# Central_Board.net
KiCad netlist of a schematic drawn in EAGLE
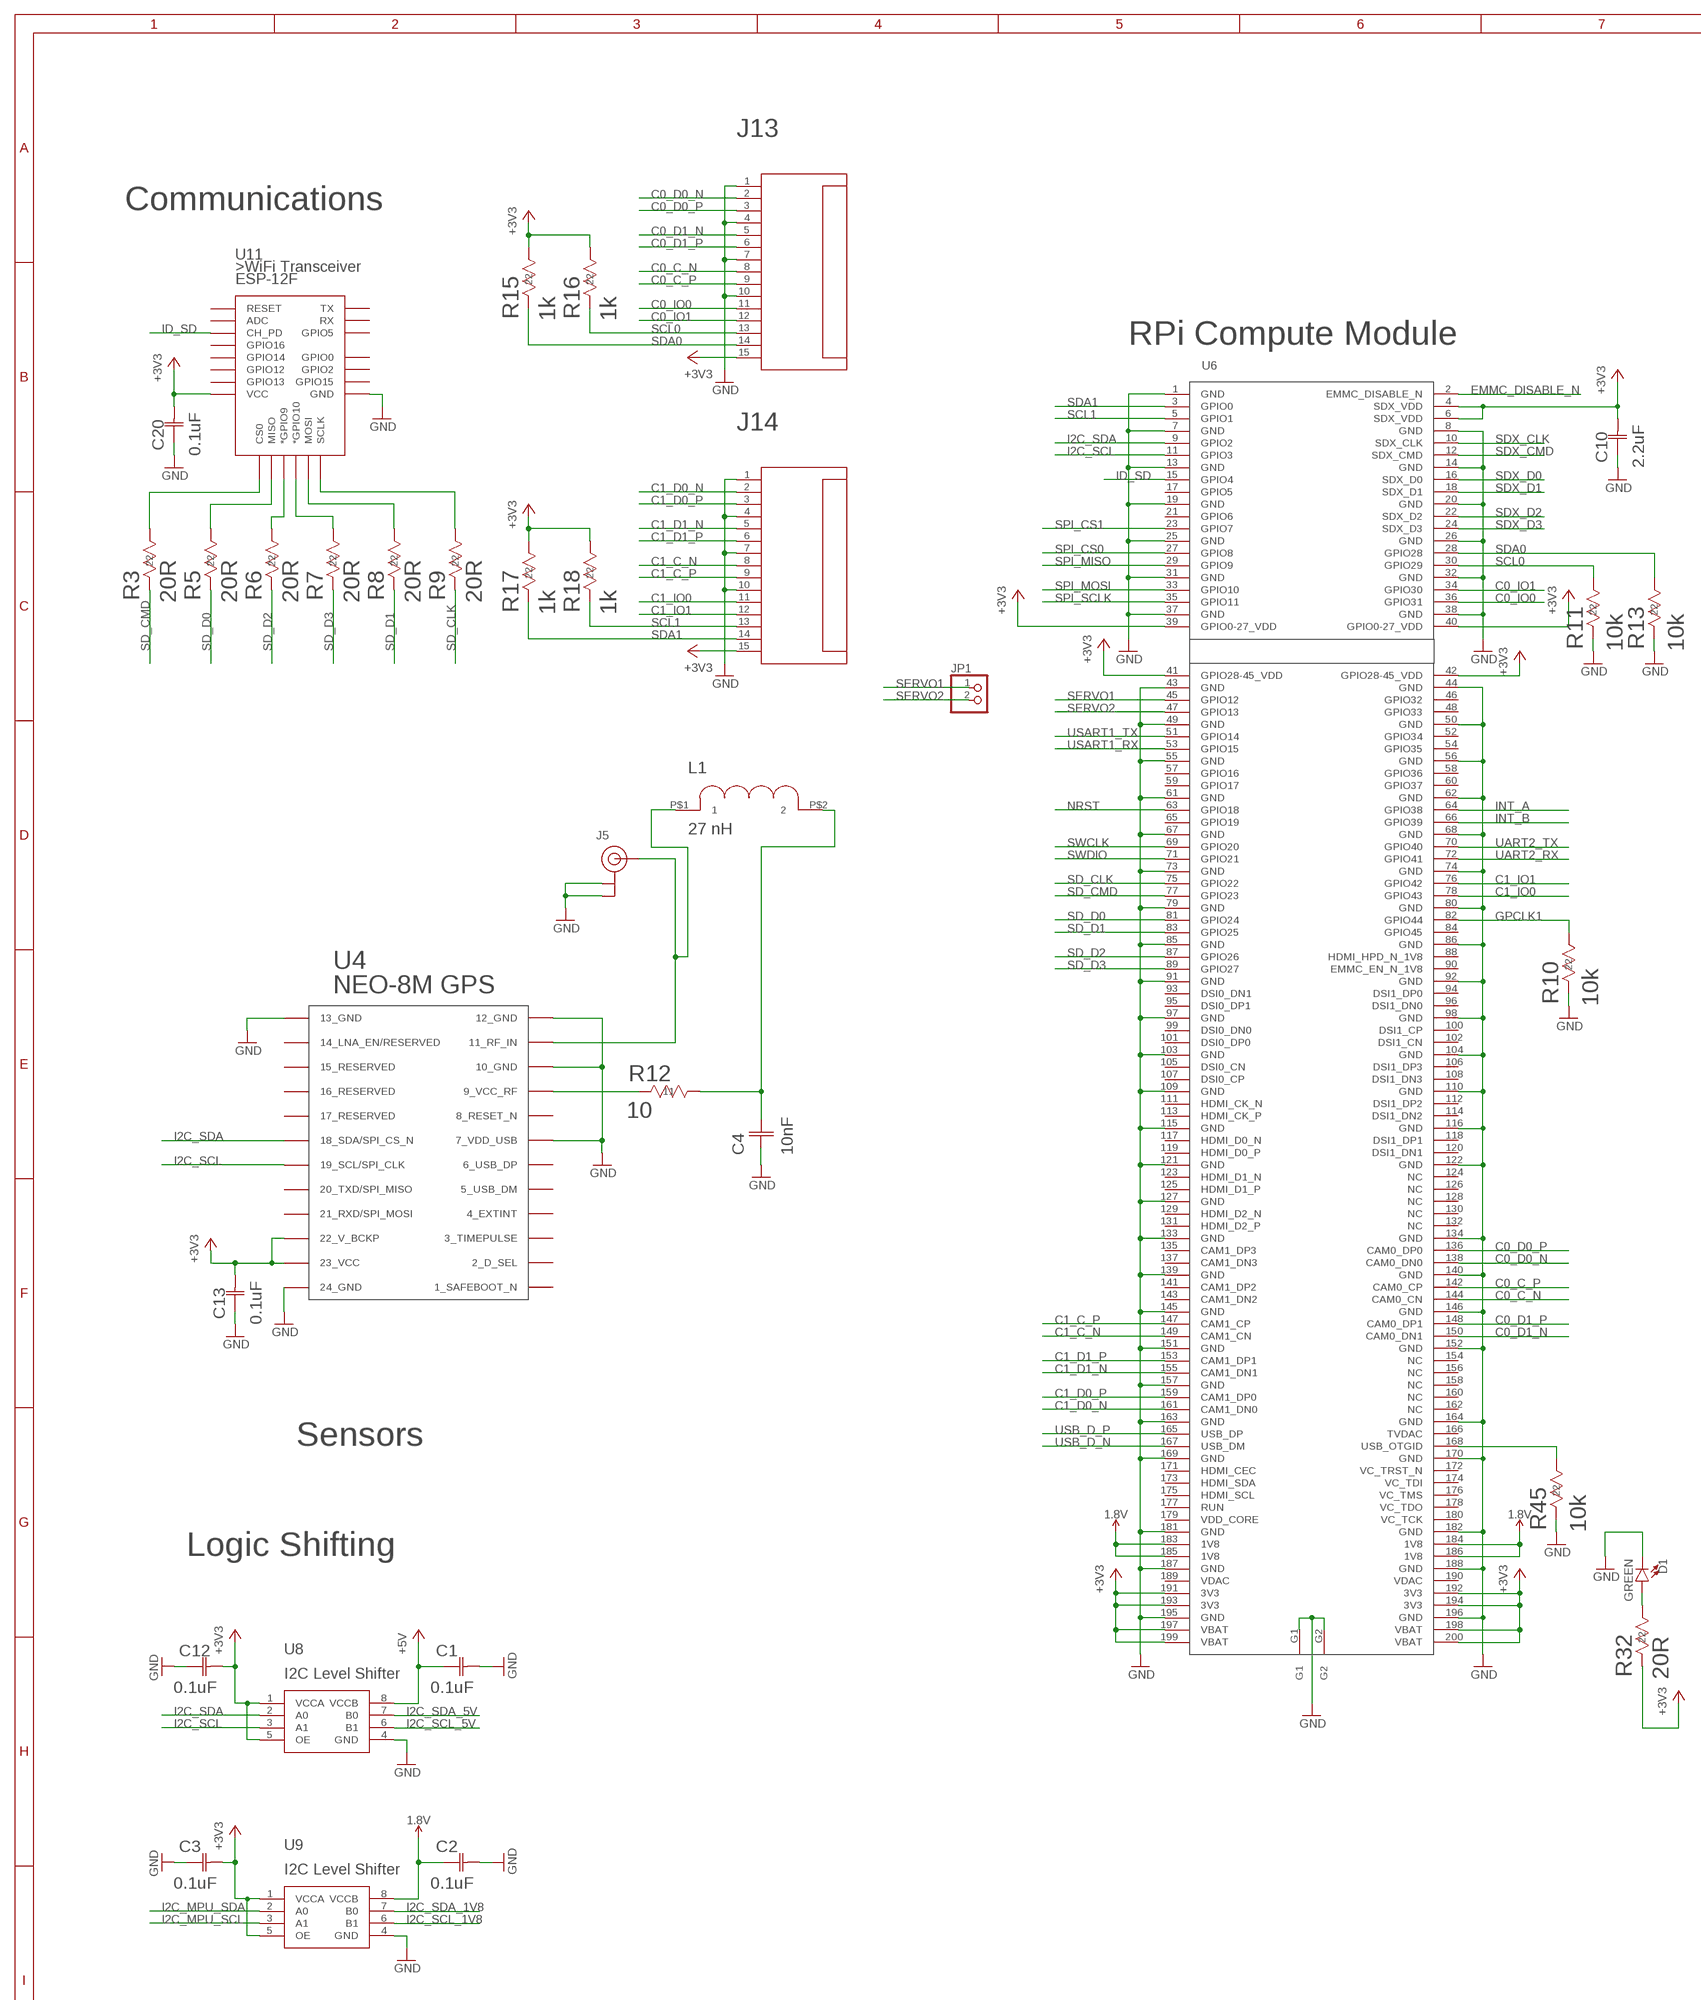
[diagram p0: schematic, sheet 1, part 1 of 2]
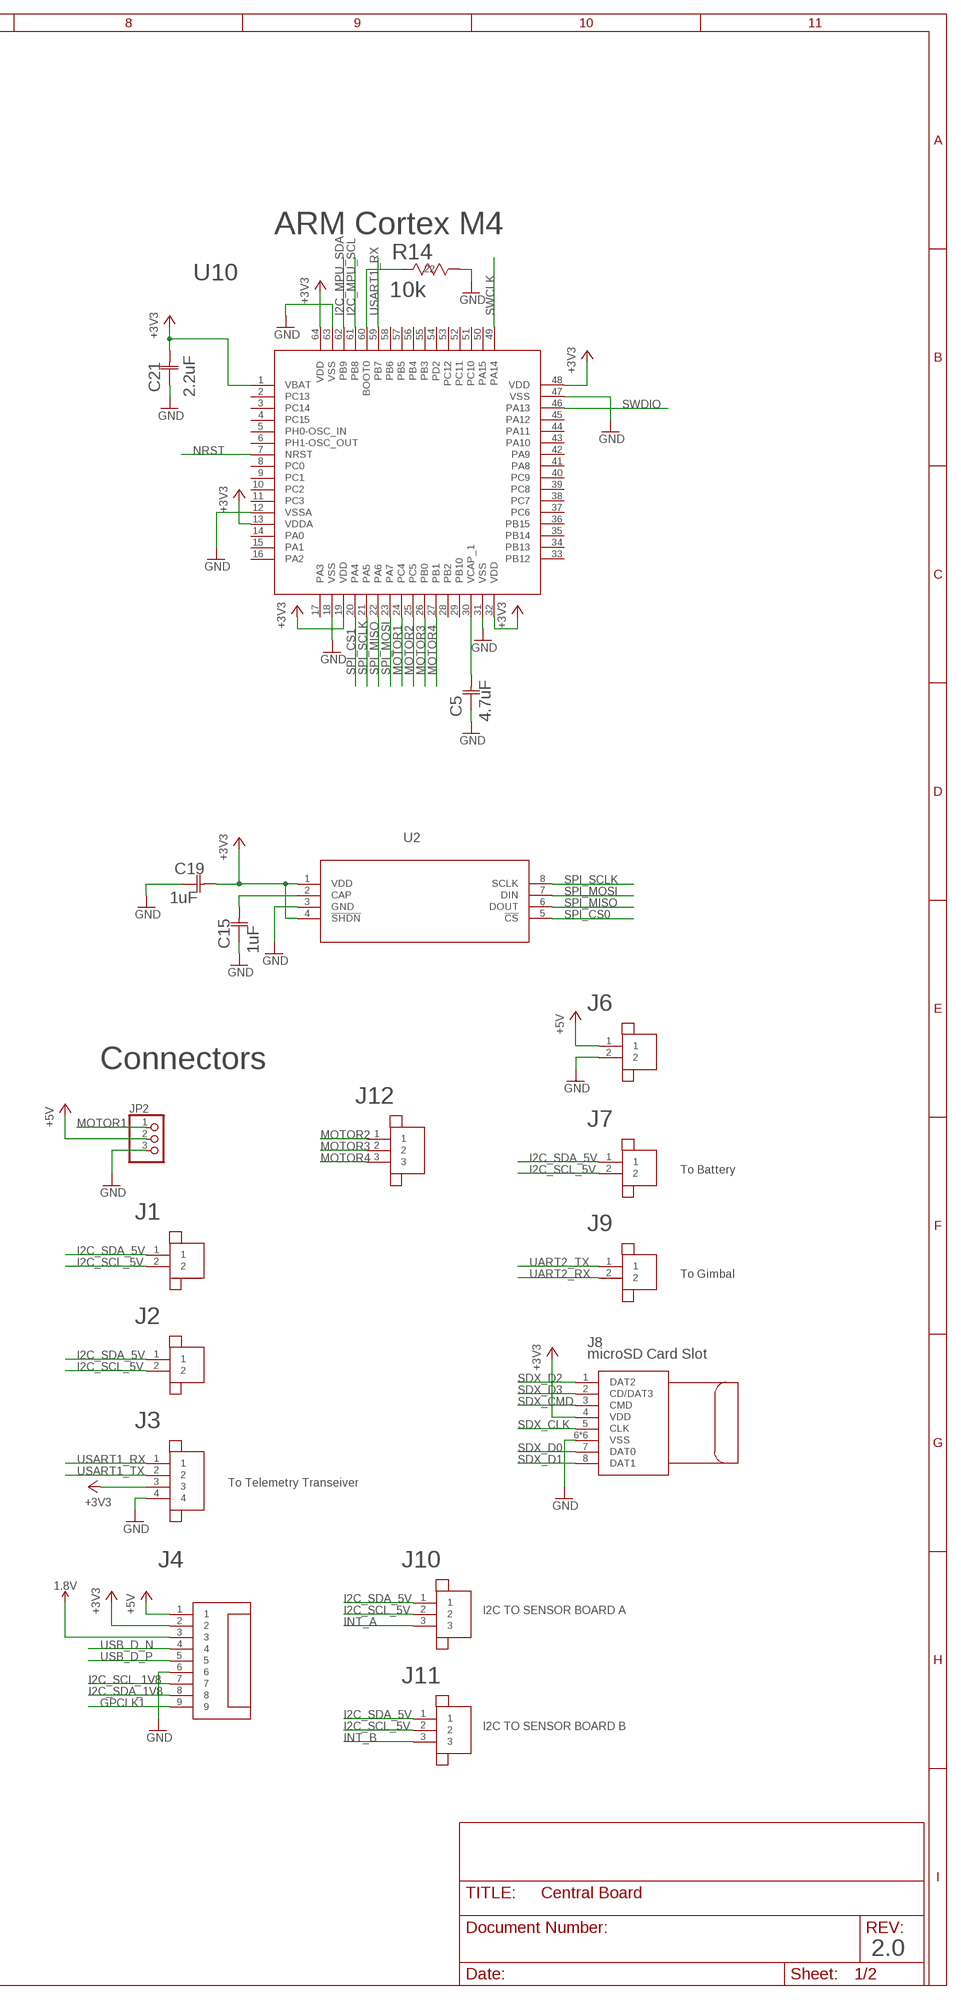
[diagram p1: schematic, sheet 1, part 2 of 2]
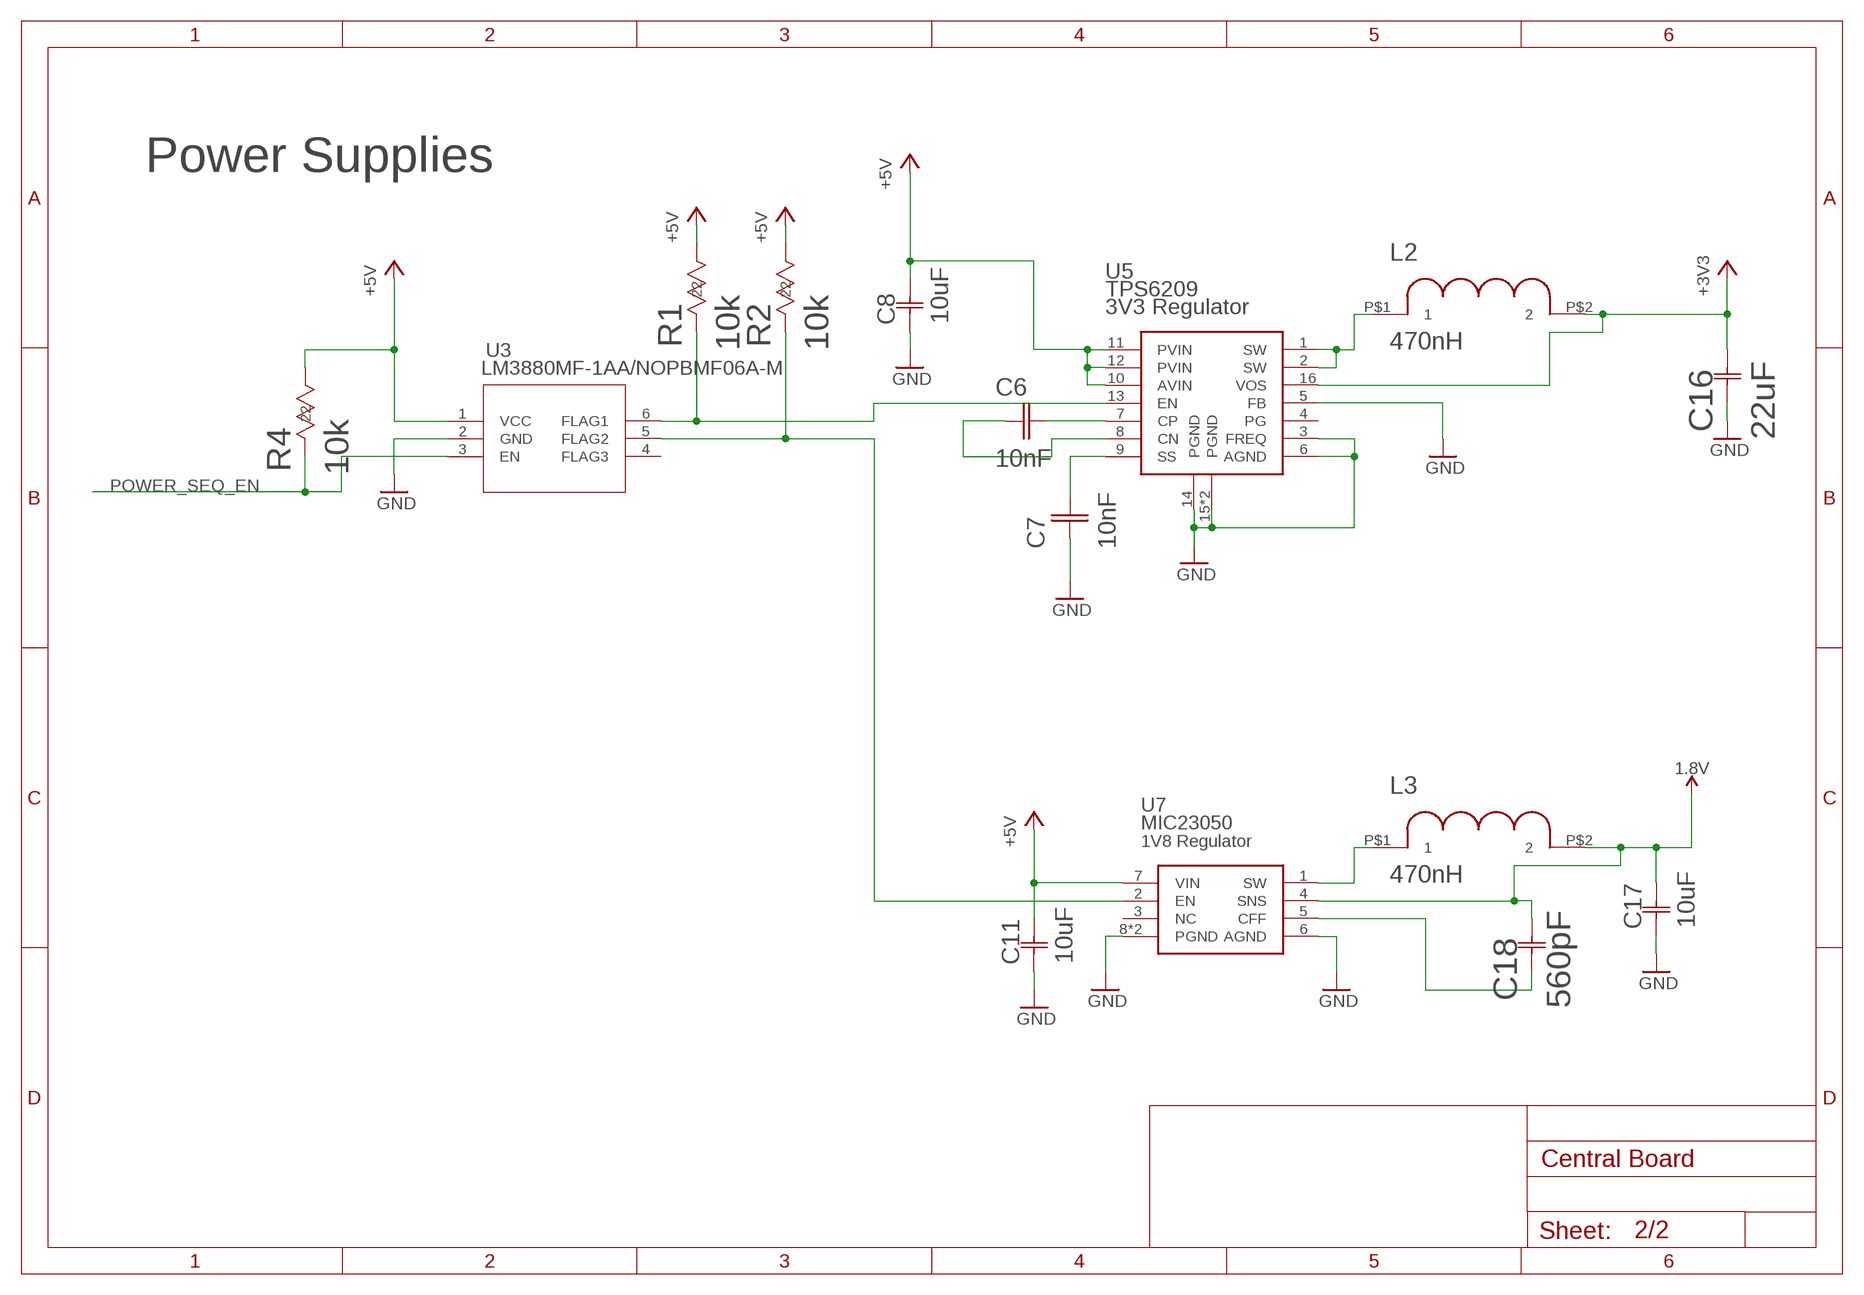
[diagram p2: schematic, sheet 2]

(export (version "E")
  (design (tool "Eeschema 10.0.6"))
  (components
    (comp (ref "C1")
      (value "0.1uF")
      (footprint "eagle-import:0805")
      (fields
        (field (name "MANUFACTURER_PART_NUMBER") "08055C104KAT2A")
        (field (name "COPYRIGHT") "Copyright C 2015 Accelerated Designs. All rights reserved")
      )
      (libsource (lib "eagle-import") (part "08055C104KAT2A"))
    )
    (comp (ref "C2")
      (value "0.1uF")
      (footprint "eagle-import:0805")
      (fields
        (field (name "MANUFACTURER_PART_NUMBER") "08055C104KAT2A")
        (field (name "COPYRIGHT") "Copyright C 2015 Accelerated Designs. All rights reserved")
      )
      (libsource (lib "eagle-import") (part "08055C104KAT2A"))
    )
    (comp (ref "C3")
      (value "0.1uF")
      (footprint "eagle-import:0805")
      (fields
        (field (name "MANUFACTURER_PART_NUMBER") "08055C104KAT2A")
        (field (name "COPYRIGHT") "Copyright C 2015 Accelerated Designs. All rights reserved")
      )
      (libsource (lib "eagle-import") (part "08055C104KAT2A"))
    )
    (comp (ref "C4")
      (value "10nF")
      (footprint "eagle-import:0603_CAPACITOR")
      (libsource (lib "eagle-import") (part "10NF_CAPACITOR"))
    )
    (comp (ref "C5")
      (value "4.7uF")
      (footprint "eagle-import:0603-M")
      (fields (field (name "MANUFACTURER_PART_NUMBER") "06036D475KAT2A"))
      (libsource (lib "eagle-import") (part "06036D475KAT2A0603-M"))
    )
    (comp (ref "C10")
      (value "2.2uF")
      (footprint "eagle-import:G-188-M")
      (fields
        (field (name "MANUFACTURER_PART_NUMBER") "GRM188R61C225KE15J")
        (field (name "COPYRIGHT") "Copyright C 2015 Accelerated Designs. All rights reserved")
      )
      (libsource (lib "eagle-import") (part "GRM188R61C225KE15JG-188-M"))
    )
    (comp (ref "C12")
      (value "0.1uF")
      (footprint "eagle-import:0805")
      (fields
        (field (name "MANUFACTURER_PART_NUMBER") "08055C104KAT2A")
        (field (name "COPYRIGHT") "Copyright C 2015 Accelerated Designs. All rights reserved")
      )
      (libsource (lib "eagle-import") (part "08055C104KAT2A"))
    )
    (comp (ref "C13")
      (value "0.1uF")
      (footprint "eagle-import:0805")
      (fields
        (field (name "MANUFACTURER_PART_NUMBER") "08055C104KAT2A")
        (field (name "COPYRIGHT") "Copyright C 2015 Accelerated Designs. All rights reserved")
      )
      (libsource (lib "eagle-import") (part "08055C104KAT2A"))
    )
    (comp (ref "C15")
      (value "1uF")
      (footprint "eagle-import:YAG_CC0805")
      (fields
        (field (name "MANUFACTURER_PART_NUMBER") "CC0805KKX7R7BB105")
        (field (name "COPYRIGHT") "Copyright C 2015 Accelerated Designs. All rights reserved")
      )
      (libsource (lib "eagle-import") (part "CC0805KKX7R7BB105"))
    )
    (comp (ref "C19")
      (value "1uF")
      (footprint "eagle-import:YAG_CC0805")
      (fields
        (field (name "MANUFACTURER_PART_NUMBER") "CC0805KKX7R7BB105")
        (field (name "COPYRIGHT") "Copyright C 2015 Accelerated Designs. All rights reserved")
      )
      (libsource (lib "eagle-import") (part "CC0805KKX7R7BB105"))
    )
    (comp (ref "C20")
      (value "0.1uF")
      (footprint "eagle-import:0805")
      (fields
        (field (name "MANUFACTURER_PART_NUMBER") "08055C104KAT2A")
        (field (name "COPYRIGHT") "Copyright C 2015 Accelerated Designs. All rights reserved")
      )
      (libsource (lib "eagle-import") (part "08055C104KAT2A"))
    )
    (comp (ref "C21")
      (value "2.2uF")
      (footprint "eagle-import:G-188-M")
      (fields
        (field (name "MANUFACTURER_PART_NUMBER") "GRM188R61C225KE15J")
        (field (name "COPYRIGHT") "Copyright C 2015 Accelerated Designs. All rights reserved")
      )
      (libsource (lib "eagle-import") (part "GRM188R61C225KE15JG-188-M"))
    )
    (comp (ref "D1")
      (value "GREEN")
      (footprint "eagle-import:LED-0603")
      (libsource (lib "eagle-import") (part "LED-GREEN0603"))
    )
    (comp (ref "J1")
      (value "JST_SH_2POS")
      (footprint "eagle-import:JST_SH_2POS")
      (libsource (lib "eagle-import") (part "JST_SH_2POS"))
    )
    (comp (ref "J2")
      (value "JST_SH_2POS")
      (footprint "eagle-import:JST_SH_2POS")
      (libsource (lib "eagle-import") (part "JST_SH_2POS"))
    )
    (comp (ref "J3")
      (value "JST_SH_4POS")
      (footprint "eagle-import:JST_SH_4POS")
      (libsource (lib "eagle-import") (part "JST_SH_4POS"))
    )
    (comp (ref "J4")
      (value "9POS_FFC_CONNECTOR")
      (footprint "eagle-import:9POS_FFC_CONNECTOR")
      (libsource (lib "eagle-import") (part "9POS_FFC_CONNECTOR"))
    )
    (comp (ref "J5")
      (value "U.FL")
      (footprint "eagle-import:U.FL")
      (libsource (lib "eagle-import") (part "U.FL"))
    )
    (comp (ref "J6")
      (value "JST_SH_2POS")
      (footprint "eagle-import:JST_SH_2POS")
      (libsource (lib "eagle-import") (part "JST_SH_2POS"))
    )
    (comp (ref "J7")
      (value "JST_SH_2POS")
      (footprint "eagle-import:JST_SH_2POS")
      (libsource (lib "eagle-import") (part "JST_SH_2POS"))
    )
    (comp (ref "J8")
      (value "MICROSD")
      (footprint "eagle-import:MICROSD")
      (libsource (lib "eagle-import") (part "MICROSD"))
    )
    (comp (ref "J9")
      (value "JST_SH_2POS")
      (footprint "eagle-import:JST_SH_2POS")
      (libsource (lib "eagle-import") (part "JST_SH_2POS"))
    )
    (comp (ref "J10")
      (value "JST_SH_3POS")
      (footprint "eagle-import:JST_SH_3POS")
      (libsource (lib "eagle-import") (part "JST_SH_3POS"))
    )
    (comp (ref "J11")
      (value "JST_SH_3POS")
      (footprint "eagle-import:JST_SH_3POS")
      (libsource (lib "eagle-import") (part "JST_SH_3POS"))
    )
    (comp (ref "J12")
      (value "JST_SH_3POS")
      (footprint "eagle-import:JST_SH_3POS")
      (libsource (lib "eagle-import") (part "JST_SH_3POS"))
    )
    (comp (ref "J13")
      (value "0526101572_15ZIF_CONNECTOR")
      (footprint "eagle-import:15POS_FFC_CONNECTOR")
      (libsource (lib "eagle-import") (part "0526101572_15ZIF_CONNECTOR"))
    )
    (comp (ref "J14")
      (value "0526101572_15ZIF_CONNECTOR")
      (footprint "eagle-import:15POS_FFC_CONNECTOR")
      (libsource (lib "eagle-import") (part "0526101572_15ZIF_CONNECTOR"))
    )
    (comp (ref "JP1")
      (value "PINHD-1X2")
      (footprint "eagle-import:1X02")
      (libsource (lib "eagle-import") (part "PINHD-1X2"))
    )
    (comp (ref "JP2")
      (value "PINHD-1X3")
      (footprint "eagle-import:1X03")
      (libsource (lib "eagle-import") (part "PINHD-1X3"))
    )
    (comp (ref "L1")
      (value "27 nH")
      (footprint "eagle-import:0402_INDUCTOR")
      (libsource (lib "eagle-import") (part "27NH_INDUCTOR"))
    )
    (comp (ref "R3")
      (value "20R")
      (footprint "eagle-import:RC0603N-M")
      (fields (field (name "MANUFACTURER_PART_NUMBER") "RC0603JR0720RL"))
      (libsource (lib "eagle-import") (part "RC0603JR-0720RLRC0603N-M"))
    )
    (comp (ref "R5")
      (value "20R")
      (footprint "eagle-import:RC0603N-M")
      (fields (field (name "MANUFACTURER_PART_NUMBER") "RC0603JR0720RL"))
      (libsource (lib "eagle-import") (part "RC0603JR-0720RLRC0603N-M"))
    )
    (comp (ref "R6")
      (value "20R")
      (footprint "eagle-import:RC0603N-M")
      (fields (field (name "MANUFACTURER_PART_NUMBER") "RC0603JR0720RL"))
      (libsource (lib "eagle-import") (part "RC0603JR-0720RLRC0603N-M"))
    )
    (comp (ref "R7")
      (value "20R")
      (footprint "eagle-import:RC0603N-M")
      (fields (field (name "MANUFACTURER_PART_NUMBER") "RC0603JR0720RL"))
      (libsource (lib "eagle-import") (part "RC0603JR-0720RLRC0603N-M"))
    )
    (comp (ref "R8")
      (value "20R")
      (footprint "eagle-import:RC0603N-M")
      (fields (field (name "MANUFACTURER_PART_NUMBER") "RC0603JR0720RL"))
      (libsource (lib "eagle-import") (part "RC0603JR-0720RLRC0603N-M"))
    )
    (comp (ref "R9")
      (value "20R")
      (footprint "eagle-import:RC0603N-M")
      (fields (field (name "MANUFACTURER_PART_NUMBER") "RC0603JR0720RL"))
      (libsource (lib "eagle-import") (part "RC0603JR-0720RLRC0603N-M"))
    )
    (comp (ref "R10")
      (value "10k")
      (footprint "eagle-import:RC0805N")
      (fields
        (field (name "DIGIKEYPARTNUMBER") "P10KDATRND")
        (field (name "MANUFACTURER_PART_NUMBER") "ERA6AEB103V")
        (field (name "TOLERANCE") "0.1%")
        (field (name "COPYRIGHT") "Copyright C 2015 Accelerated Designs. All rights reserved")
      )
      (libsource (lib "eagle-import") (part "ERA-6AEB103V"))
    )
    (comp (ref "R11")
      (value "10k")
      (footprint "eagle-import:RC0805N")
      (fields
        (field (name "DIGIKEYPARTNUMBER") "P10KDATRND")
        (field (name "MANUFACTURER_PART_NUMBER") "ERA6AEB103V")
        (field (name "TOLERANCE") "0.1%")
        (field (name "COPYRIGHT") "Copyright C 2015 Accelerated Designs. All rights reserved")
      )
      (libsource (lib "eagle-import") (part "ERA-6AEB103V"))
    )
    (comp (ref "R12")
      (value "10")
      (footprint "eagle-import:STA_RNCP0805-M")
      (fields
        (field (name "MANUFACTURER_PART_NUMBER") "RNCP0805FTD10R0")
        (field (name "COPYRIGHT") "Copyright C 2015 Accelerated Designs. All rights reserved")
      )
      (libsource (lib "eagle-import") (part "RNCP0805FTD10R0STA_RNCP0805-M"))
    )
    (comp (ref "R13")
      (value "10k")
      (footprint "eagle-import:RC0805N")
      (fields
        (field (name "DIGIKEYPARTNUMBER") "P10KDATRND")
        (field (name "MANUFACTURER_PART_NUMBER") "ERA6AEB103V")
        (field (name "TOLERANCE") "0.1%")
        (field (name "COPYRIGHT") "Copyright C 2015 Accelerated Designs. All rights reserved")
      )
      (libsource (lib "eagle-import") (part "ERA-6AEB103V"))
    )
    (comp (ref "R14")
      (value "10k")
      (footprint "eagle-import:RC0805N")
      (fields
        (field (name "DIGIKEYPARTNUMBER") "P10KDATRND")
        (field (name "MANUFACTURER_PART_NUMBER") "ERA6AEB103V")
        (field (name "TOLERANCE") "0.1%")
        (field (name "COPYRIGHT") "Copyright C 2015 Accelerated Designs. All rights reserved")
      )
      (libsource (lib "eagle-import") (part "ERA-6AEB103V"))
    )
    (comp (ref "R15")
      (value "1k")
      (footprint "eagle-import:RC0603N-M")
      (fields
        (field (name "DIGIKEYPARTNUMBER") "3111.0KGRTRND")
        (field (name "MANUFACTURER_PART_NUMBER") "RC0603JR071KL")
        (field (name "NEWARKPARTNUMBER") "14M7231")
        (field (name "COPYRIGHT") "Copyright C 2015 Accelerated Designs. All rights reserved")
      )
      (libsource (lib "eagle-import") (part "RC0603JR-071KLRC0603N-M"))
    )
    (comp (ref "R16")
      (value "1k")
      (footprint "eagle-import:RC0603N-M")
      (fields
        (field (name "DIGIKEYPARTNUMBER") "3111.0KGRTRND")
        (field (name "MANUFACTURER_PART_NUMBER") "RC0603JR071KL")
        (field (name "NEWARKPARTNUMBER") "14M7231")
        (field (name "COPYRIGHT") "Copyright C 2015 Accelerated Designs. All rights reserved")
      )
      (libsource (lib "eagle-import") (part "RC0603JR-071KLRC0603N-M"))
    )
    (comp (ref "R17")
      (value "1k")
      (footprint "eagle-import:RC0603N-M")
      (fields
        (field (name "DIGIKEYPARTNUMBER") "3111.0KGRTRND")
        (field (name "MANUFACTURER_PART_NUMBER") "RC0603JR071KL")
        (field (name "NEWARKPARTNUMBER") "14M7231")
        (field (name "COPYRIGHT") "Copyright C 2015 Accelerated Designs. All rights reserved")
      )
      (libsource (lib "eagle-import") (part "RC0603JR-071KLRC0603N-M"))
    )
    (comp (ref "R18")
      (value "1k")
      (footprint "eagle-import:RC0603N-M")
      (fields
        (field (name "DIGIKEYPARTNUMBER") "3111.0KGRTRND")
        (field (name "MANUFACTURER_PART_NUMBER") "RC0603JR071KL")
        (field (name "NEWARKPARTNUMBER") "14M7231")
        (field (name "COPYRIGHT") "Copyright C 2015 Accelerated Designs. All rights reserved")
      )
      (libsource (lib "eagle-import") (part "RC0603JR-071KLRC0603N-M"))
    )
    (comp (ref "R32")
      (value "20R")
      (footprint "eagle-import:RC0603N-M")
      (fields (field (name "MANUFACTURER_PART_NUMBER") "RC0603JR0720RL"))
      (libsource (lib "eagle-import") (part "RC0603JR-0720RLRC0603N-M"))
    )
    (comp (ref "R45")
      (value "10k")
      (footprint "eagle-import:RC0805N")
      (fields
        (field (name "DIGIKEYPARTNUMBER") "P10KDATRND")
        (field (name "MANUFACTURER_PART_NUMBER") "ERA6AEB103V")
        (field (name "TOLERANCE") "0.1%")
        (field (name "COPYRIGHT") "Copyright C 2015 Accelerated Designs. All rights reserved")
      )
      (libsource (lib "eagle-import") (part "ERA-6AEB103V"))
    )
    (comp (ref "U2")
      (value "MPL115A1LGA8-M")
      (footprint "eagle-import:LGA8-M")
      (fields (field (name "MANUFACTURER_PART_NUMBER") "mpl115a1"))
      (libsource (lib "eagle-import") (part "MPL115A1LGA8-M"))
    )
    (comp (ref "U4")
      (value "NEO-M8")
      (footprint "eagle-import:NEO-M8")
      (libsource (lib "eagle-import") (part "NEO-M8"))
    )
    (comp (ref "U6")
      (value "COMPUTE_MODULE")
      (footprint "eagle-import:SO-DIMM")
      (libsource (lib "eagle-import") (part "COMPUTE_MODULE"))
    )
    (comp (ref "U8")
      (value "FXMAR2102")
      (footprint "eagle-import:8-UMLP")
      (libsource (lib "eagle-import") (part "FXMAR2102"))
    )
    (comp (ref "U9")
      (value "FXMAR2102")
      (footprint "eagle-import:8-UMLP")
      (libsource (lib "eagle-import") (part "FXMAR2102"))
    )
    (comp (ref "U10")
      (value "STM32F446")
      (footprint "eagle-import:LQFP64")
      (libsource (lib "eagle-import") (part "STM32F446"))
    )
    (comp (ref "U11")
      (value "ESP12ESMD")
      (footprint "eagle-import:ESP12E-SMD")
      (libsource (lib "eagle-import") (part "ESP12ESMD"))
    )
    (comp (ref "C6")
      (value "10nF")
      (footprint "eagle-import:0603_CAPACITOR")
      (libsource (lib "eagle-import") (part "10NF_CAPACITOR"))
    )
    (comp (ref "C7")
      (value "10nF")
      (footprint "eagle-import:0603_CAPACITOR")
      (libsource (lib "eagle-import") (part "10NF_CAPACITOR"))
    )
    (comp (ref "C8")
      (value "10uF")
      (footprint "eagle-import:G-21")
      (fields
        (field (name "MANUFACTURER_PART_NUMBER") "GRM21BR60J106ME19L")
        (field (name "COPYRIGHT") "Copyright C 2015 Accelerated Designs. All rights reserved")
      )
      (libsource (lib "eagle-import") (part "GRM21BR60J106ME19L"))
    )
    (comp (ref "C11")
      (value "10uF")
      (footprint "eagle-import:G-21")
      (fields
        (field (name "MANUFACTURER_PART_NUMBER") "GRM21BR60J106ME19L")
        (field (name "COPYRIGHT") "Copyright C 2015 Accelerated Designs. All rights reserved")
      )
      (libsource (lib "eagle-import") (part "GRM21BR60J106ME19L"))
    )
    (comp (ref "C16")
      (value "22uF")
      (footprint "eagle-import:G-21")
      (fields
        (field (name "MANUFACTURER_PART_NUMBER") "GRM21BR60J226ME39L")
        (field (name "COPYRIGHT") "Copyright C 2015 Accelerated Designs. All rights reserved")
      )
      (libsource (lib "eagle-import") (part "GRM21BR60J226ME39L"))
    )
    (comp (ref "C17")
      (value "10uF")
      (footprint "eagle-import:G-21")
      (fields
        (field (name "MANUFACTURER_PART_NUMBER") "GRM21BR60J106ME19L")
        (field (name "COPYRIGHT") "Copyright C 2015 Accelerated Designs. All rights reserved")
      )
      (libsource (lib "eagle-import") (part "GRM21BR60J106ME19L"))
    )
    (comp (ref "C18")
      (value "560pF")
      (footprint "eagle-import:CC0402N-M")
      (fields (field (name "MANUFACTURER_PART_NUMBER") "CC0402KRX7R9BB561"))
      (libsource (lib "eagle-import") (part "CC0402KRX7R9BB561CC0402N-M"))
    )
    (comp (ref "L2")
      (value "470nH")
      (footprint "eagle-import:1008_INDUCTOR")
      (libsource (lib "eagle-import") (part "470NH_INDUCTOR"))
    )
    (comp (ref "L3")
      (value "470nH")
      (footprint "eagle-import:1008_INDUCTOR")
      (libsource (lib "eagle-import") (part "470NH_INDUCTOR"))
    )
    (comp (ref "R1")
      (value "10k")
      (footprint "eagle-import:RC0805N")
      (fields
        (field (name "DIGIKEYPARTNUMBER") "P10KDATRND")
        (field (name "MANUFACTURER_PART_NUMBER") "ERA6AEB103V")
        (field (name "TOLERANCE") "0.1%")
        (field (name "COPYRIGHT") "Copyright C 2015 Accelerated Designs. All rights reserved")
      )
      (libsource (lib "eagle-import") (part "ERA-6AEB103V"))
    )
    (comp (ref "R2")
      (value "10k")
      (footprint "eagle-import:RC0805N")
      (fields
        (field (name "DIGIKEYPARTNUMBER") "P10KDATRND")
        (field (name "MANUFACTURER_PART_NUMBER") "ERA6AEB103V")
        (field (name "TOLERANCE") "0.1%")
        (field (name "COPYRIGHT") "Copyright C 2015 Accelerated Designs. All rights reserved")
      )
      (libsource (lib "eagle-import") (part "ERA-6AEB103V"))
    )
    (comp (ref "R4")
      (value "10k")
      (footprint "eagle-import:RC0805N")
      (fields
        (field (name "DIGIKEYPARTNUMBER") "P10KDATRND")
        (field (name "MANUFACTURER_PART_NUMBER") "ERA6AEB103V")
        (field (name "TOLERANCE") "0.1%")
        (field (name "COPYRIGHT") "Copyright C 2015 Accelerated Designs. All rights reserved")
      )
      (libsource (lib "eagle-import") (part "ERA-6AEB103V"))
    )
    (comp (ref "U3")
      (value "LM3880MF-1AA/NOPBMF06A-M")
      (footprint "eagle-import:MF06A-M")
      (fields (field (name "MANUFACTURER_PART_NUMBER") "lm3880mf1aaNOPB"))
      (libsource (lib "eagle-import") (part "LM3880MF-1AA/NOPBMF06A-M"))
    )
    (comp (ref "U5")
      (value "TPS6209")
      (footprint "eagle-import:VQFN16")
      (libsource (lib "eagle-import") (part "TPS6209"))
    )
    (comp (ref "U7")
      (value "MIC23050")
      (footprint "eagle-import:MLF(ML)_8PIN")
      (libsource (lib "eagle-import") (part "MIC23050"))
    )
  )
  (nets
    (net (code "1") (name "+3V3") (class "Default")
      (node (ref "C10") (pin "2") (pinfunction "22_2") (pintype "passive"))
      (node (ref "C12") (pin "2") (pinfunction "2_2") (pintype "passive"))
      (node (ref "C13") (pin "2") (pinfunction "2_2") (pintype "passive"))
      (node (ref "C16") (pin "2") (pinfunction "22_2") (pintype "passive"))
      (node (ref "C19") (pin "2") (pinfunction "22_2") (pintype "passive"))
      (node (ref "C20") (pin "2") (pinfunction "2_2") (pintype "passive"))
      (node (ref "C21") (pin "2") (pinfunction "22_2") (pintype "passive"))
      (node (ref "C3") (pin "2") (pinfunction "2_2") (pintype "passive"))
      (node (ref "J13") (pin "15") (pinfunction "15_15") (pintype "bidirectional"))
      (node (ref "J14") (pin "15") (pinfunction "15_15") (pintype "bidirectional"))
      (node (ref "J3") (pin "3") (pinfunction "3_3") (pintype "bidirectional"))
      (node (ref "J4") (pin "2") (pinfunction "2_2") (pintype "bidirectional"))
      (node (ref "J8") (pin "4") (pinfunction "VDD_4") (pintype "bidirectional"))
      (node (ref "L2") (pin "P$2") (pinfunction "2_P$2") (pintype "passive"))
      (node (ref "R15") (pin "1") (pinfunction "11_1") (pintype "passive"))
      (node (ref "R16") (pin "1") (pinfunction "11_1") (pintype "passive"))
      (node (ref "R17") (pin "1") (pinfunction "11_1") (pintype "passive"))
      (node (ref "R18") (pin "1") (pinfunction "11_1") (pintype "passive"))
      (node (ref "R32") (pin "2") (pinfunction "22_2") (pintype "passive"))
      (node (ref "U10") (pin "1") (pinfunction "VBAT_1") (pintype "bidirectional"))
      (node (ref "U10") (pin "13") (pinfunction "VDDA_13") (pintype "bidirectional"))
      (node (ref "U10") (pin "19") (pinfunction "VDD_19") (pintype "bidirectional"))
      (node (ref "U10") (pin "32") (pinfunction "VDD_32") (pintype "bidirectional"))
      (node (ref "U10") (pin "48") (pinfunction "VDD_48") (pintype "bidirectional"))
      (node (ref "U10") (pin "64") (pinfunction "VDD_64") (pintype "bidirectional"))
      (node (ref "U11") (pin "VCC") (pinfunction "VCC_VCC") (pintype "bidirectional"))
      (node (ref "U2") (pin "1") (pinfunction "VDD_1") (pintype "power_in"))
      (node (ref "U2") (pin "4") (pinfunction "~{SHDN}_4") (pintype "passive"))
      (node (ref "U4") (pin "22") (pinfunction "22_V_BCKP_22") (pintype "bidirectional"))
      (node (ref "U4") (pin "23") (pinfunction "23_VCC_23") (pintype "bidirectional"))
      (node (ref "U5") (pin "16") (pinfunction "VOS_16") (pintype "bidirectional"))
      (node (ref "U6") (pin "191") (pinfunction "3V3_191") (pintype "bidirectional"))
      (node (ref "U6") (pin "192") (pinfunction "3V3_192") (pintype "bidirectional"))
      (node (ref "U6") (pin "193") (pinfunction "3V3_193") (pintype "bidirectional"))
      (node (ref "U6") (pin "194") (pinfunction "3V3_194") (pintype "bidirectional"))
      (node (ref "U6") (pin "197") (pinfunction "VBAT_197") (pintype "bidirectional"))
      (node (ref "U6") (pin "198") (pinfunction "VBAT_198") (pintype "bidirectional"))
      (node (ref "U6") (pin "199") (pinfunction "VBAT_199") (pintype "bidirectional"))
      (node (ref "U6") (pin "200") (pinfunction "VBAT_200") (pintype "bidirectional"))
      (node (ref "U6") (pin "39") (pinfunction "GPIO0-27_VDD_39") (pintype "bidirectional"))
      (node (ref "U6") (pin "4") (pinfunction "SDX_VDD_4") (pintype "bidirectional"))
      (node (ref "U6") (pin "40") (pinfunction "GPIO0-27_VDD_40") (pintype "bidirectional"))
      (node (ref "U6") (pin "41") (pinfunction "GPIO28-45_VDD_41") (pintype "bidirectional"))
      (node (ref "U6") (pin "42") (pinfunction "GPIO28-45_VDD_42") (pintype "bidirectional"))
      (node (ref "U6") (pin "6") (pinfunction "SDX_VDD_6") (pintype "bidirectional"))
      (node (ref "U8") (pin "1") (pinfunction "VCCA_1") (pintype "bidirectional"))
      (node (ref "U8") (pin "5") (pinfunction "OE_5") (pintype "bidirectional"))
      (node (ref "U9") (pin "1") (pinfunction "VCCA_1") (pintype "bidirectional"))
      (node (ref "U9") (pin "5") (pinfunction "OE_5") (pintype "bidirectional"))
    )
    (net (code "2") (name "+5V") (class "Default")
      (node (ref "C1") (pin "1") (pinfunction "1_1") (pintype "passive"))
      (node (ref "C11") (pin "2") (pinfunction "22_2") (pintype "passive"))
      (node (ref "C8") (pin "2") (pinfunction "22_2") (pintype "passive"))
      (node (ref "J4") (pin "1") (pinfunction "1_1") (pintype "bidirectional"))
      (node (ref "J6") (pin "1") (pinfunction "1_1") (pintype "bidirectional"))
      (node (ref "JP2") (pin "2") (pinfunction "2_2") (pintype "passive"))
      (node (ref "R1") (pin "1") (pinfunction "11_1") (pintype "passive"))
      (node (ref "R2") (pin "1") (pinfunction "11_1") (pintype "passive"))
      (node (ref "R4") (pin "1") (pinfunction "11_1") (pintype "passive"))
      (node (ref "U3") (pin "1") (pinfunction "VCC_1") (pintype "power_in"))
      (node (ref "U5") (pin "10") (pinfunction "AVIN_10") (pintype "bidirectional"))
      (node (ref "U5") (pin "11") (pinfunction "PVIN_11") (pintype "bidirectional"))
      (node (ref "U5") (pin "12") (pinfunction "PVIN_12") (pintype "bidirectional"))
      (node (ref "U7") (pin "7") (pinfunction "VIN_7") (pintype "bidirectional"))
      (node (ref "U8") (pin "8") (pinfunction "VCCB_8") (pintype "bidirectional"))
    )
    (net (code "3") (name "1.8V") (class "Default")
      (node (ref "C17") (pin "2") (pinfunction "22_2") (pintype "passive"))
      (node (ref "C18") (pin "2") (pinfunction "22_2") (pintype "passive"))
      (node (ref "C2") (pin "1") (pinfunction "1_1") (pintype "passive"))
      (node (ref "J4") (pin "3") (pinfunction "3_3") (pintype "bidirectional"))
      (node (ref "L3") (pin "P$2") (pinfunction "2_P$2") (pintype "passive"))
      (node (ref "U6") (pin "183") (pinfunction "1V8_183") (pintype "bidirectional"))
      (node (ref "U6") (pin "184") (pinfunction "1V8_184") (pintype "bidirectional"))
      (node (ref "U6") (pin "185") (pinfunction "1V8_185") (pintype "bidirectional"))
      (node (ref "U6") (pin "186") (pinfunction "1V8_186") (pintype "bidirectional"))
      (node (ref "U7") (pin "4") (pinfunction "SNS_4") (pintype "bidirectional"))
      (node (ref "U9") (pin "8") (pinfunction "VCCB_8") (pintype "bidirectional"))
    )
    (net (code "4") (name "C0_C_N") (class "Default")
      (node (ref "J13") (pin "8") (pinfunction "8_8") (pintype "bidirectional"))
      (node (ref "U6") (pin "144") (pinfunction "CAM0_CN_144") (pintype "bidirectional"))
    )
    (net (code "5") (name "C0_C_P") (class "Default")
      (node (ref "J13") (pin "9") (pinfunction "9_9") (pintype "bidirectional"))
      (node (ref "U6") (pin "142") (pinfunction "CAM0_CP_142") (pintype "bidirectional"))
    )
    (net (code "6") (name "C0_D0_N") (class "Default")
      (node (ref "J13") (pin "2") (pinfunction "2_2") (pintype "bidirectional"))
      (node (ref "U6") (pin "138") (pinfunction "CAM0_DN0_138") (pintype "bidirectional"))
    )
    (net (code "7") (name "C0_D0_P") (class "Default")
      (node (ref "J13") (pin "3") (pinfunction "3_3") (pintype "bidirectional"))
      (node (ref "U6") (pin "136") (pinfunction "CAM0_DP0_136") (pintype "bidirectional"))
    )
    (net (code "8") (name "C0_D1_N") (class "Default")
      (node (ref "J13") (pin "5") (pinfunction "5_5") (pintype "bidirectional"))
      (node (ref "U6") (pin "150") (pinfunction "CAM0_DN1_150") (pintype "bidirectional"))
    )
    (net (code "9") (name "C0_D1_P") (class "Default")
      (node (ref "J13") (pin "6") (pinfunction "6_6") (pintype "bidirectional"))
      (node (ref "U6") (pin "148") (pinfunction "CAM0_DP1_148") (pintype "bidirectional"))
    )
    (net (code "10") (name "C0_IO0") (class "Default")
      (node (ref "J13") (pin "11") (pinfunction "11_11") (pintype "bidirectional"))
      (node (ref "U6") (pin "36") (pinfunction "GPIO31_36") (pintype "bidirectional"))
    )
    (net (code "11") (name "C0_IO1") (class "Default")
      (node (ref "J13") (pin "12") (pinfunction "12_12") (pintype "bidirectional"))
      (node (ref "U6") (pin "34") (pinfunction "GPIO30_34") (pintype "bidirectional"))
    )
    (net (code "12") (name "C1_C_N") (class "Default")
      (node (ref "J14") (pin "8") (pinfunction "8_8") (pintype "bidirectional"))
      (node (ref "U6") (pin "149") (pinfunction "CAM1_CN_149") (pintype "bidirectional"))
    )
    (net (code "13") (name "C1_C_P") (class "Default")
      (node (ref "J14") (pin "9") (pinfunction "9_9") (pintype "bidirectional"))
      (node (ref "U6") (pin "147") (pinfunction "CAM1_CP_147") (pintype "bidirectional"))
    )
    (net (code "14") (name "C1_D0_N") (class "Default")
      (node (ref "J14") (pin "2") (pinfunction "2_2") (pintype "bidirectional"))
      (node (ref "U6") (pin "161") (pinfunction "CAM1_DN0_161") (pintype "bidirectional"))
    )
    (net (code "15") (name "C1_D0_P") (class "Default")
      (node (ref "J14") (pin "3") (pinfunction "3_3") (pintype "bidirectional"))
      (node (ref "U6") (pin "159") (pinfunction "CAM1_DP0_159") (pintype "bidirectional"))
    )
    (net (code "16") (name "C1_D1_N") (class "Default")
      (node (ref "J14") (pin "5") (pinfunction "5_5") (pintype "bidirectional"))
      (node (ref "U6") (pin "155") (pinfunction "CAM1_DN1_155") (pintype "bidirectional"))
    )
    (net (code "17") (name "C1_D1_P") (class "Default")
      (node (ref "J14") (pin "6") (pinfunction "6_6") (pintype "bidirectional"))
      (node (ref "U6") (pin "153") (pinfunction "CAM1_DP1_153") (pintype "bidirectional"))
    )
    (net (code "18") (name "C1_IO0") (class "Default")
      (node (ref "J14") (pin "11") (pinfunction "11_11") (pintype "bidirectional"))
      (node (ref "U6") (pin "78") (pinfunction "GPIO43_78") (pintype "bidirectional"))
    )
    (net (code "19") (name "C1_IO1") (class "Default")
      (node (ref "J14") (pin "12") (pinfunction "12_12") (pintype "bidirectional"))
      (node (ref "U6") (pin "76") (pinfunction "GPIO42_76") (pintype "bidirectional"))
    )
    (net (code "20") (name "EMMC_DISABLE_N") (class "Default")
      (node (ref "U6") (pin "2") (pinfunction "EMMC_DISABLE_N_2") (pintype "bidirectional"))
    )
    (net (code "21") (name "GND") (class "Default")
      (node (ref "C1") (pin "2") (pinfunction "2_2") (pintype "passive"))
      (node (ref "C10") (pin "1") (pinfunction "11_1") (pintype "passive"))
      (node (ref "C11") (pin "1") (pinfunction "11_1") (pintype "passive"))
      (node (ref "C12") (pin "1") (pinfunction "1_1") (pintype "passive"))
      (node (ref "C13") (pin "1") (pinfunction "1_1") (pintype "passive"))
      (node (ref "C15") (pin "1") (pinfunction "11_1") (pintype "passive"))
      (node (ref "C16") (pin "1") (pinfunction "11_1") (pintype "passive"))
      (node (ref "C17") (pin "1") (pinfunction "11_1") (pintype "passive"))
      (node (ref "C19") (pin "1") (pinfunction "11_1") (pintype "passive"))
      (node (ref "C2") (pin "2") (pinfunction "2_2") (pintype "passive"))
      (node (ref "C20") (pin "1") (pinfunction "1_1") (pintype "passive"))
      (node (ref "C21") (pin "1") (pinfunction "11_1") (pintype "passive"))
      (node (ref "C3") (pin "1") (pinfunction "1_1") (pintype "passive"))
      (node (ref "C4") (pin "1") (pinfunction "1_1") (pintype "bidirectional"))
      (node (ref "C5") (pin "1") (pinfunction "1_1") (pintype "passive"))
      (node (ref "C7") (pin "1") (pinfunction "1_1") (pintype "bidirectional"))
      (node (ref "C8") (pin "1") (pinfunction "11_1") (pintype "passive"))
      (node (ref "D1") (pin "C") (pinfunction "C_C") (pintype "passive"))
      (node (ref "J13") (pin "1") (pinfunction "1_1") (pintype "bidirectional"))
      (node (ref "J13") (pin "10") (pinfunction "10_10") (pintype "bidirectional"))
      (node (ref "J13") (pin "4") (pinfunction "4_4") (pintype "bidirectional"))
      (node (ref "J13") (pin "7") (pinfunction "7_7") (pintype "bidirectional"))
      (node (ref "J14") (pin "1") (pinfunction "1_1") (pintype "bidirectional"))
      (node (ref "J14") (pin "10") (pinfunction "10_10") (pintype "bidirectional"))
      (node (ref "J14") (pin "4") (pinfunction "4_4") (pintype "bidirectional"))
      (node (ref "J14") (pin "7") (pinfunction "7_7") (pintype "bidirectional"))
      (node (ref "J3") (pin "4") (pinfunction "4_4") (pintype "bidirectional"))
      (node (ref "J4") (pin "6") (pinfunction "6_6") (pintype "bidirectional"))
      (node (ref "J5") (pin "P$1") (pinfunction "GND_P$1") (pintype "bidirectional"))
      (node (ref "J5") (pin "P$2") (pinfunction "GND_P$2") (pintype "bidirectional"))
      (node (ref "J6") (pin "2") (pinfunction "2_2") (pintype "bidirectional"))
      (node (ref "J8") (pin "10") (pinfunction "VSS_10") (pintype "bidirectional"))
      (node (ref "J8") (pin "11") (pinfunction "VSS_11") (pintype "bidirectional"))
      (node (ref "J8") (pin "12") (pinfunction "VSS_12") (pintype "bidirectional"))
      (node (ref "J8") (pin "13") (pinfunction "VSS_13") (pintype "bidirectional"))
      (node (ref "J8") (pin "6") (pinfunction "VSS_6") (pintype "bidirectional"))
      (node (ref "J8") (pin "9") (pinfunction "VSS_9") (pintype "bidirectional"))
      (node (ref "JP2") (pin "3") (pinfunction "3_3") (pintype "passive"))
      (node (ref "R10") (pin "2") (pinfunction "22_2") (pintype "passive"))
      (node (ref "R11") (pin "2") (pinfunction "22_2") (pintype "passive"))
      (node (ref "R13") (pin "2") (pinfunction "22_2") (pintype "passive"))
      (node (ref "R14") (pin "1") (pinfunction "11_1") (pintype "passive"))
      (node (ref "R45") (pin "2") (pinfunction "22_2") (pintype "passive"))
      (node (ref "U10") (pin "12") (pinfunction "VSSA_12") (pintype "bidirectional"))
      (node (ref "U10") (pin "18") (pinfunction "VSS_18") (pintype "bidirectional"))
      (node (ref "U10") (pin "31") (pinfunction "VSS_31") (pintype "bidirectional"))
      (node (ref "U10") (pin "47") (pinfunction "VSS_47") (pintype "bidirectional"))
      (node (ref "U10") (pin "63") (pinfunction "VSS_63") (pintype "bidirectional"))
      (node (ref "U11") (pin "GND") (pinfunction "GND_GND") (pintype "bidirectional"))
      (node (ref "U2") (pin "3") (pinfunction "GND_3") (pintype "power_in"))
      (node (ref "U3") (pin "2") (pinfunction "GND_2") (pintype "power_in"))
      (node (ref "U4") (pin "10") (pinfunction "10_GND_10") (pintype "bidirectional"))
      (node (ref "U4") (pin "12") (pinfunction "12_GND_12") (pintype "bidirectional"))
      (node (ref "U4") (pin "13") (pinfunction "13_GND_13") (pintype "bidirectional"))
      (node (ref "U4") (pin "24") (pinfunction "24_GND_24") (pintype "bidirectional"))
      (node (ref "U4") (pin "7") (pinfunction "7_VDD_USB_7") (pintype "bidirectional"))
      (node (ref "U5") (pin "14") (pinfunction "PGND_14") (pintype "bidirectional"))
      (node (ref "U5") (pin "15") (pinfunction "PGND_15") (pintype "bidirectional"))
      (node (ref "U5") (pin "17") (pinfunction "PGND_17") (pintype "bidirectional"))
      (node (ref "U5") (pin "3") (pinfunction "FREQ_3") (pintype "bidirectional"))
      (node (ref "U5") (pin "5") (pinfunction "FB_5") (pintype "bidirectional"))
      (node (ref "U5") (pin "6") (pinfunction "AGND_6") (pintype "bidirectional"))
      (node (ref "U6") (pin "1") (pinfunction "GND_1") (pintype "bidirectional"))
      (node (ref "U6") (pin "103") (pinfunction "GND_103") (pintype "bidirectional"))
      (node (ref "U6") (pin "104") (pinfunction "GND_104") (pintype "bidirectional"))
      (node (ref "U6") (pin "109") (pinfunction "GND_109") (pintype "bidirectional"))
      (node (ref "U6") (pin "110") (pinfunction "GND_110") (pintype "bidirectional"))
      (node (ref "U6") (pin "115") (pinfunction "GND_115") (pintype "bidirectional"))
      (node (ref "U6") (pin "116") (pinfunction "GND_116") (pintype "bidirectional"))
      (node (ref "U6") (pin "121") (pinfunction "GND_121") (pintype "bidirectional"))
      (node (ref "U6") (pin "122") (pinfunction "GND_122") (pintype "bidirectional"))
      (node (ref "U6") (pin "127") (pinfunction "GND_127") (pintype "bidirectional"))
      (node (ref "U6") (pin "13") (pinfunction "GND_13") (pintype "bidirectional"))
      (node (ref "U6") (pin "133") (pinfunction "GND_133") (pintype "bidirectional"))
      (node (ref "U6") (pin "134") (pinfunction "GND_134") (pintype "bidirectional"))
      (node (ref "U6") (pin "139") (pinfunction "GND_139") (pintype "bidirectional"))
      (node (ref "U6") (pin "14") (pinfunction "GND_14") (pintype "bidirectional"))
      (node (ref "U6") (pin "140") (pinfunction "GND_140") (pintype "bidirectional"))
      (node (ref "U6") (pin "145") (pinfunction "GND_145") (pintype "bidirectional"))
      (node (ref "U6") (pin "146") (pinfunction "GND_146") (pintype "bidirectional"))
      (node (ref "U6") (pin "151") (pinfunction "GND_151") (pintype "bidirectional"))
      (node (ref "U6") (pin "152") (pinfunction "GND_152") (pintype "bidirectional"))
      (node (ref "U6") (pin "157") (pinfunction "GND_157") (pintype "bidirectional"))
      (node (ref "U6") (pin "163") (pinfunction "GND_163") (pintype "bidirectional"))
      (node (ref "U6") (pin "164") (pinfunction "GND_164") (pintype "bidirectional"))
      (node (ref "U6") (pin "169") (pinfunction "GND_169") (pintype "bidirectional"))
      (node (ref "U6") (pin "170") (pinfunction "GND_170") (pintype "bidirectional"))
      (node (ref "U6") (pin "181") (pinfunction "GND_181") (pintype "bidirectional"))
      (node (ref "U6") (pin "182") (pinfunction "GND_182") (pintype "bidirectional"))
      (node (ref "U6") (pin "187") (pinfunction "GND_187") (pintype "bidirectional"))
      (node (ref "U6") (pin "188") (pinfunction "GND_188") (pintype "bidirectional"))
      (node (ref "U6") (pin "19") (pinfunction "GND_19") (pintype "bidirectional"))
      (node (ref "U6") (pin "195") (pinfunction "GND_195") (pintype "bidirectional"))
      (node (ref "U6") (pin "196") (pinfunction "GND_196") (pintype "bidirectional"))
      (node (ref "U6") (pin "20") (pinfunction "GND_20") (pintype "bidirectional"))
      (node (ref "U6") (pin "25") (pinfunction "GND_25") (pintype "bidirectional"))
      (node (ref "U6") (pin "26") (pinfunction "GND_26") (pintype "bidirectional"))
      (node (ref "U6") (pin "31") (pinfunction "GND_31") (pintype "bidirectional"))
      (node (ref "U6") (pin "32") (pinfunction "GND_32") (pintype "bidirectional"))
      (node (ref "U6") (pin "37") (pinfunction "GND_37") (pintype "bidirectional"))
      (node (ref "U6") (pin "38") (pinfunction "GND_38") (pintype "bidirectional"))
      (node (ref "U6") (pin "43") (pinfunction "GND_43") (pintype "bidirectional"))
      (node (ref "U6") (pin "44") (pinfunction "GND_44") (pintype "bidirectional"))
      (node (ref "U6") (pin "49") (pinfunction "GND_49") (pintype "bidirectional"))
      (node (ref "U6") (pin "50") (pinfunction "GND_50") (pintype "bidirectional"))
      (node (ref "U6") (pin "55") (pinfunction "GND_55") (pintype "bidirectional"))
      (node (ref "U6") (pin "56") (pinfunction "GND_56") (pintype "bidirectional"))
      (node (ref "U6") (pin "61") (pinfunction "GND_61") (pintype "bidirectional"))
      (node (ref "U6") (pin "62") (pinfunction "GND_62") (pintype "bidirectional"))
      (node (ref "U6") (pin "67") (pinfunction "GND_67") (pintype "bidirectional"))
      (node (ref "U6") (pin "68") (pinfunction "GND_68") (pintype "bidirectional"))
      (node (ref "U6") (pin "7") (pinfunction "GND_7") (pintype "bidirectional"))
      (node (ref "U6") (pin "73") (pinfunction "GND_73") (pintype "bidirectional"))
      (node (ref "U6") (pin "74") (pinfunction "GND_74") (pintype "bidirectional"))
      (node (ref "U6") (pin "79") (pinfunction "GND_79") (pintype "bidirectional"))
      (node (ref "U6") (pin "8") (pinfunction "GND_8") (pintype "bidirectional"))
      (node (ref "U6") (pin "80") (pinfunction "GND_80") (pintype "bidirectional"))
      (node (ref "U6") (pin "85") (pinfunction "GND_85") (pintype "bidirectional"))
      (node (ref "U6") (pin "86") (pinfunction "GND_86") (pintype "bidirectional"))
      (node (ref "U6") (pin "91") (pinfunction "GND_91") (pintype "bidirectional"))
      (node (ref "U6") (pin "92") (pinfunction "GND_92") (pintype "bidirectional"))
      (node (ref "U6") (pin "97") (pinfunction "GND_97") (pintype "bidirectional"))
      (node (ref "U6") (pin "98") (pinfunction "GND_98") (pintype "bidirectional"))
      (node (ref "U6") (pin "G1") (pinfunction "G1_G1") (pintype "bidirectional"))
      (node (ref "U6") (pin "G2") (pinfunction "G2_G2") (pintype "bidirectional"))
      (node (ref "U7") (pin "6") (pinfunction "AGND_6") (pintype "bidirectional"))
      (node (ref "U7") (pin "8") (pinfunction "PGND_8") (pintype "bidirectional"))
      (node (ref "U7") (pin "EP") (pinfunction "PGND_EP") (pintype "bidirectional"))
      (node (ref "U8") (pin "4") (pinfunction "GND_4") (pintype "bidirectional"))
      (node (ref "U9") (pin "4") (pinfunction "GND_4") (pintype "bidirectional"))
    )
    (net (code "22") (name "GPCLK1") (class "Default")
      (node (ref "J4") (pin "9") (pinfunction "9_9") (pintype "bidirectional"))
      (node (ref "R10") (pin "1") (pinfunction "11_1") (pintype "passive"))
      (node (ref "U6") (pin "82") (pinfunction "GPIO44_82") (pintype "bidirectional"))
    )
    (net (code "23") (name "I2C_MPU_SCL") (class "Default")
      (node (ref "U10") (pin "61") (pinfunction "PB8_61") (pintype "bidirectional"))
      (node (ref "U9") (pin "3") (pinfunction "A1_3") (pintype "bidirectional"))
    )
    (net (code "24") (name "I2C_MPU_SDA") (class "Default")
      (node (ref "U10") (pin "62") (pinfunction "PB9_62") (pintype "bidirectional"))
      (node (ref "U9") (pin "2") (pinfunction "A0_2") (pintype "bidirectional"))
    )
    (net (code "25") (name "I2C_SCL") (class "Default")
      (node (ref "U4") (pin "19") (pinfunction "19_SCL/SPI_CLK_19") (pintype "bidirectional"))
      (node (ref "U6") (pin "11") (pinfunction "GPIO3_11") (pintype "bidirectional"))
      (node (ref "U8") (pin "3") (pinfunction "A1_3") (pintype "bidirectional"))
    )
    (net (code "26") (name "I2C_SCL_1V8") (class "Default")
      (node (ref "J4") (pin "7") (pinfunction "7_7") (pintype "bidirectional"))
      (node (ref "U9") (pin "6") (pinfunction "B1_6") (pintype "bidirectional"))
    )
    (net (code "27") (name "I2C_SCL_5V") (class "Default")
      (node (ref "J1") (pin "2") (pinfunction "2_2") (pintype "bidirectional"))
      (node (ref "J10") (pin "2") (pinfunction "2_2") (pintype "bidirectional"))
      (node (ref "J11") (pin "2") (pinfunction "2_2") (pintype "bidirectional"))
      (node (ref "J2") (pin "2") (pinfunction "2_2") (pintype "bidirectional"))
      (node (ref "J7") (pin "2") (pinfunction "2_2") (pintype "bidirectional"))
      (node (ref "U8") (pin "6") (pinfunction "B1_6") (pintype "bidirectional"))
    )
    (net (code "28") (name "I2C_SDA") (class "Default")
      (node (ref "U4") (pin "18") (pinfunction "18_SDA/SPI_CS_N_18") (pintype "bidirectional"))
      (node (ref "U6") (pin "9") (pinfunction "GPIO2_9") (pintype "bidirectional"))
      (node (ref "U8") (pin "2") (pinfunction "A0_2") (pintype "bidirectional"))
    )
    (net (code "29") (name "I2C_SDA_1V8") (class "Default")
      (node (ref "J4") (pin "8") (pinfunction "8_8") (pintype "bidirectional"))
      (node (ref "U9") (pin "7") (pinfunction "B0_7") (pintype "bidirectional"))
    )
    (net (code "30") (name "I2C_SDA_5V") (class "Default")
      (node (ref "J1") (pin "1") (pinfunction "1_1") (pintype "bidirectional"))
      (node (ref "J10") (pin "1") (pinfunction "1_1") (pintype "bidirectional"))
      (node (ref "J11") (pin "1") (pinfunction "1_1") (pintype "bidirectional"))
      (node (ref "J2") (pin "1") (pinfunction "1_1") (pintype "bidirectional"))
      (node (ref "J7") (pin "1") (pinfunction "1_1") (pintype "bidirectional"))
      (node (ref "U8") (pin "7") (pinfunction "B0_7") (pintype "bidirectional"))
    )
    (net (code "31") (name "ID_SD") (class "Default")
      (node (ref "U11") (pin "CH_PD") (pinfunction "CH_PD_CH_PD") (pintype "bidirectional"))
      (node (ref "U6") (pin "15") (pinfunction "GPIO4_15") (pintype "bidirectional"))
    )
    (net (code "32") (name "INT_A") (class "Default")
      (node (ref "J10") (pin "3") (pinfunction "3_3") (pintype "bidirectional"))
      (node (ref "U6") (pin "64") (pinfunction "GPIO38_64") (pintype "bidirectional"))
    )
    (net (code "33") (name "INT_B") (class "Default")
      (node (ref "J11") (pin "3") (pinfunction "3_3") (pintype "bidirectional"))
      (node (ref "U6") (pin "66") (pinfunction "GPIO39_66") (pintype "bidirectional"))
    )
    (net (code "34") (name "MOTOR1") (class "Default")
      (node (ref "JP2") (pin "1") (pinfunction "1_1") (pintype "passive"))
      (node (ref "U10") (pin "24") (pinfunction "PC4_24") (pintype "bidirectional"))
    )
    (net (code "35") (name "MOTOR2") (class "Default")
      (node (ref "J12") (pin "1") (pinfunction "1_1") (pintype "bidirectional"))
      (node (ref "U10") (pin "25") (pinfunction "PC5_25") (pintype "bidirectional"))
    )
    (net (code "36") (name "MOTOR3") (class "Default")
      (node (ref "J12") (pin "2") (pinfunction "2_2") (pintype "bidirectional"))
      (node (ref "U10") (pin "26") (pinfunction "PB0_26") (pintype "bidirectional"))
    )
    (net (code "37") (name "MOTOR4") (class "Default")
      (node (ref "J12") (pin "3") (pinfunction "3_3") (pintype "bidirectional"))
      (node (ref "U10") (pin "27") (pinfunction "PB1_27") (pintype "bidirectional"))
    )
    (net (code "38") (name "NRST") (class "Default")
      (node (ref "U10") (pin "7") (pinfunction "NRST_7") (pintype "bidirectional"))
      (node (ref "U6") (pin "63") (pinfunction "GPIO18_63") (pintype "bidirectional"))
    )
    (net (code "39") (name "Net-(C15-22)") (class "Default")
      (node (ref "C15") (pin "2") (pinfunction "22_2") (pintype "passive"))
      (node (ref "U2") (pin "2") (pinfunction "CAP_2") (pintype "output"))
    )
    (net (code "40") (name "Net-(C18-11)") (class "Default")
      (node (ref "C18") (pin "1") (pinfunction "11_1") (pintype "passive"))
      (node (ref "U7") (pin "5") (pinfunction "CFF_5") (pintype "bidirectional"))
    )
    (net (code "41") (name "Net-(J5-SIGNAL)") (class "Default")
      (node (ref "J5") (pin "P$3") (pinfunction "SIGNAL_P$3") (pintype "bidirectional"))
      (node (ref "L1") (pin "P$1") (pinfunction "1_P$1") (pintype "passive"))
      (node (ref "U4") (pin "11") (pinfunction "11_RF_IN_11") (pintype "bidirectional"))
    )
    (net (code "42") (name "Net-(L1-2)") (class "Default")
      (node (ref "C4") (pin "2") (pinfunction "2_2") (pintype "bidirectional"))
      (node (ref "L1") (pin "P$2") (pinfunction "2_P$2") (pintype "passive"))
      (node (ref "R12") (pin "2") (pinfunction "22_2") (pintype "passive"))
    )
    (net (code "43") (name "Net-(L2-1)") (class "Default")
      (node (ref "L2") (pin "P$1") (pinfunction "1_P$1") (pintype "passive"))
      (node (ref "U5") (pin "1") (pinfunction "SW_1") (pintype "bidirectional"))
      (node (ref "U5") (pin "2") (pinfunction "SW_2") (pintype "bidirectional"))
    )
    (net (code "44") (name "Net-(L3-1)") (class "Default")
      (node (ref "L3") (pin "P$1") (pinfunction "1_P$1") (pintype "passive"))
      (node (ref "U7") (pin "1") (pinfunction "SW_1") (pintype "bidirectional"))
    )
    (net (code "45") (name "Net-(R1-22)") (class "Default")
      (node (ref "R1") (pin "2") (pinfunction "22_2") (pintype "passive"))
      (node (ref "U3") (pin "6") (pinfunction "FLAG1_6") (pintype "passive"))
      (node (ref "U5") (pin "13") (pinfunction "EN_13") (pintype "bidirectional"))
    )
    (net (code "46") (name "Net-(R2-22)") (class "Default")
      (node (ref "R2") (pin "2") (pinfunction "22_2") (pintype "passive"))
      (node (ref "U3") (pin "5") (pinfunction "FLAG2_5") (pintype "passive"))
      (node (ref "U7") (pin "2") (pinfunction "EN_2") (pintype "bidirectional"))
    )
    (net (code "47") (name "Net-(R3-11)") (class "Default")
      (node (ref "R3") (pin "1") (pinfunction "11_1") (pintype "passive"))
      (node (ref "U11") (pin "CS0") (pinfunction "CS0_CS0") (pintype "bidirectional"))
    )
    (net (code "48") (name "Net-(R5-11)") (class "Default")
      (node (ref "R5") (pin "1") (pinfunction "11_1") (pintype "passive"))
      (node (ref "U11") (pin "MISO") (pinfunction "MISO_MISO") (pintype "bidirectional"))
    )
    (net (code "49") (name "Net-(R6-11)") (class "Default")
      (node (ref "R6") (pin "1") (pinfunction "11_1") (pintype "passive"))
      (node (ref "U11") (pin "GPIO9") (pinfunction "*GPIO9_GPIO9") (pintype "bidirectional"))
    )
    (net (code "50") (name "Net-(R7-11)") (class "Default")
      (node (ref "R7") (pin "1") (pinfunction "11_1") (pintype "passive"))
      (node (ref "U11") (pin "GPIO10") (pinfunction "*GPIO10_GPIO10") (pintype "bidirectional"))
    )
    (net (code "51") (name "Net-(R8-11)") (class "Default")
      (node (ref "R8") (pin "1") (pinfunction "11_1") (pintype "passive"))
      (node (ref "U11") (pin "MOSI") (pinfunction "MOSI_MOSI") (pintype "bidirectional"))
    )
    (net (code "52") (name "Net-(R9-11)") (class "Default")
      (node (ref "R9") (pin "1") (pinfunction "11_1") (pintype "passive"))
      (node (ref "U11") (pin "SCLK") (pinfunction "SCLK_SCLK") (pintype "bidirectional"))
    )
    (net (code "53") (name "Net-(R12-11)") (class "Default")
      (node (ref "R12") (pin "1") (pinfunction "11_1") (pintype "passive"))
      (node (ref "U4") (pin "9") (pinfunction "9_VCC_RF_9") (pintype "bidirectional"))
    )
    (net (code "54") (name "Net-(R14-22)") (class "Default")
      (node (ref "R14") (pin "2") (pinfunction "22_2") (pintype "passive"))
      (node (ref "U10") (pin "60") (pinfunction "BOOT0_60") (pintype "bidirectional"))
    )
    (net (code "55") (name "Net-(R32-11)") (class "Default")
      (node (ref "D1") (pin "A") (pinfunction "A_A") (pintype "passive"))
      (node (ref "R32") (pin "1") (pinfunction "11_1") (pintype "passive"))
    )
    (net (code "56") (name "Net-(R45-11)") (class "Default")
      (node (ref "R45") (pin "1") (pinfunction "11_1") (pintype "passive"))
      (node (ref "U6") (pin "168") (pinfunction "USB_OTGID_168") (pintype "bidirectional"))
    )
    (net (code "57") (name "Net-(U5-CN)") (class "Default")
      (node (ref "C6") (pin "1") (pinfunction "1_1") (pintype "bidirectional"))
      (node (ref "U5") (pin "8") (pinfunction "CN_8") (pintype "bidirectional"))
    )
    (net (code "58") (name "Net-(U5-CP)") (class "Default")
      (node (ref "C6") (pin "2") (pinfunction "2_2") (pintype "bidirectional"))
      (node (ref "U5") (pin "7") (pinfunction "CP_7") (pintype "bidirectional"))
    )
    (net (code "59") (name "Net-(U5-SS)") (class "Default")
      (node (ref "C7") (pin "2") (pinfunction "2_2") (pintype "bidirectional"))
      (node (ref "U5") (pin "9") (pinfunction "SS_9") (pintype "bidirectional"))
    )
    (net (code "60") (name "Net-(U10-VCAP_1)") (class "Default")
      (node (ref "C5") (pin "2") (pinfunction "2_2") (pintype "passive"))
      (node (ref "U10") (pin "30") (pinfunction "VCAP_1_30") (pintype "bidirectional"))
    )
    (net (code "61") (name "POWER_SEQ_EN") (class "Default")
      (node (ref "R4") (pin "2") (pinfunction "22_2") (pintype "passive"))
      (node (ref "U3") (pin "3") (pinfunction "EN_3") (pintype "input"))
    )
    (net (code "62") (name "SCL0") (class "Default")
      (node (ref "J13") (pin "13") (pinfunction "13_13") (pintype "bidirectional"))
      (node (ref "R11") (pin "1") (pinfunction "11_1") (pintype "passive"))
      (node (ref "R16") (pin "2") (pinfunction "22_2") (pintype "passive"))
      (node (ref "U6") (pin "30") (pinfunction "GPIO29_30") (pintype "bidirectional"))
    )
    (net (code "63") (name "SCL1") (class "Default")
      (node (ref "J14") (pin "13") (pinfunction "13_13") (pintype "bidirectional"))
      (node (ref "R18") (pin "2") (pinfunction "22_2") (pintype "passive"))
      (node (ref "U6") (pin "5") (pinfunction "GPIO1_5") (pintype "bidirectional"))
    )
    (net (code "64") (name "SDA0") (class "Default")
      (node (ref "J13") (pin "14") (pinfunction "14_14") (pintype "bidirectional"))
      (node (ref "R13") (pin "1") (pinfunction "11_1") (pintype "passive"))
      (node (ref "R15") (pin "2") (pinfunction "22_2") (pintype "passive"))
      (node (ref "U6") (pin "28") (pinfunction "GPIO28_28") (pintype "bidirectional"))
    )
    (net (code "65") (name "SDA1") (class "Default")
      (node (ref "J14") (pin "14") (pinfunction "14_14") (pintype "bidirectional"))
      (node (ref "R17") (pin "2") (pinfunction "22_2") (pintype "passive"))
      (node (ref "U6") (pin "3") (pinfunction "GPIO0_3") (pintype "bidirectional"))
    )
    (net (code "66") (name "SDX_CLK") (class "Default")
      (node (ref "J8") (pin "5") (pinfunction "CLK_5") (pintype "bidirectional"))
      (node (ref "U6") (pin "10") (pinfunction "SDX_CLK_10") (pintype "bidirectional"))
    )
    (net (code "67") (name "SDX_CMD") (class "Default")
      (node (ref "J8") (pin "3") (pinfunction "CMD_3") (pintype "bidirectional"))
      (node (ref "U6") (pin "12") (pinfunction "SDX_CMD_12") (pintype "bidirectional"))
    )
    (net (code "68") (name "SDX_D0") (class "Default")
      (node (ref "J8") (pin "7") (pinfunction "DAT0_7") (pintype "bidirectional"))
      (node (ref "U6") (pin "16") (pinfunction "SDX_D0_16") (pintype "bidirectional"))
    )
    (net (code "69") (name "SDX_D1") (class "Default")
      (node (ref "J8") (pin "8") (pinfunction "DAT1_8") (pintype "bidirectional"))
      (node (ref "U6") (pin "18") (pinfunction "SDX_D1_18") (pintype "bidirectional"))
    )
    (net (code "70") (name "SDX_D2") (class "Default")
      (node (ref "J8") (pin "1") (pinfunction "DAT2_1") (pintype "bidirectional"))
      (node (ref "U6") (pin "22") (pinfunction "SDX_D2_22") (pintype "bidirectional"))
    )
    (net (code "71") (name "SDX_D3") (class "Default")
      (node (ref "J8") (pin "2") (pinfunction "CD/DAT3_2") (pintype "bidirectional"))
      (node (ref "U6") (pin "24") (pinfunction "SDX_D3_24") (pintype "bidirectional"))
    )
    (net (code "72") (name "SD_CLK") (class "Default")
      (node (ref "R9") (pin "2") (pinfunction "22_2") (pintype "passive"))
      (node (ref "U6") (pin "75") (pinfunction "GPIO22_75") (pintype "bidirectional"))
    )
    (net (code "73") (name "SD_CMD") (class "Default")
      (node (ref "R3") (pin "2") (pinfunction "22_2") (pintype "passive"))
      (node (ref "U6") (pin "77") (pinfunction "GPIO23_77") (pintype "bidirectional"))
    )
    (net (code "74") (name "SD_D0") (class "Default")
      (node (ref "R5") (pin "2") (pinfunction "22_2") (pintype "passive"))
      (node (ref "U6") (pin "81") (pinfunction "GPIO24_81") (pintype "bidirectional"))
    )
    (net (code "75") (name "SD_D1") (class "Default")
      (node (ref "R8") (pin "2") (pinfunction "22_2") (pintype "passive"))
      (node (ref "U6") (pin "83") (pinfunction "GPIO25_83") (pintype "bidirectional"))
    )
    (net (code "76") (name "SD_D2") (class "Default")
      (node (ref "R6") (pin "2") (pinfunction "22_2") (pintype "passive"))
      (node (ref "U6") (pin "87") (pinfunction "GPIO26_87") (pintype "bidirectional"))
    )
    (net (code "77") (name "SD_D3") (class "Default")
      (node (ref "R7") (pin "2") (pinfunction "22_2") (pintype "passive"))
      (node (ref "U6") (pin "89") (pinfunction "GPIO27_89") (pintype "bidirectional"))
    )
    (net (code "78") (name "SERVO1") (class "Default")
      (node (ref "JP1") (pin "1") (pinfunction "1_1") (pintype "passive"))
      (node (ref "U6") (pin "45") (pinfunction "GPIO12_45") (pintype "bidirectional"))
    )
    (net (code "79") (name "SERVO2") (class "Default")
      (node (ref "JP1") (pin "2") (pinfunction "2_2") (pintype "passive"))
      (node (ref "U6") (pin "47") (pinfunction "GPIO13_47") (pintype "bidirectional"))
    )
    (net (code "80") (name "SPI_CS0") (class "Default")
      (node (ref "U2") (pin "5") (pinfunction "~{CS}_5") (pintype "passive"))
      (node (ref "U6") (pin "27") (pinfunction "GPIO8_27") (pintype "bidirectional"))
    )
    (net (code "81") (name "SPI_CS1") (class "Default")
      (node (ref "U10") (pin "20") (pinfunction "PA4_20") (pintype "bidirectional"))
      (node (ref "U6") (pin "23") (pinfunction "GPIO7_23") (pintype "bidirectional"))
    )
    (net (code "82") (name "SPI_MISO") (class "Default")
      (node (ref "U10") (pin "22") (pinfunction "PA6_22") (pintype "bidirectional"))
      (node (ref "U2") (pin "6") (pinfunction "DOUT_6") (pintype "output"))
      (node (ref "U6") (pin "29") (pinfunction "GPIO9_29") (pintype "bidirectional"))
    )
    (net (code "83") (name "SPI_MOSI") (class "Default")
      (node (ref "U10") (pin "23") (pinfunction "PA7_23") (pintype "bidirectional"))
      (node (ref "U2") (pin "7") (pinfunction "DIN_7") (pintype "input"))
      (node (ref "U6") (pin "33") (pinfunction "GPIO10_33") (pintype "bidirectional"))
    )
    (net (code "84") (name "SPI_SCLK") (class "Default")
      (node (ref "U10") (pin "21") (pinfunction "PA5_21") (pintype "bidirectional"))
      (node (ref "U2") (pin "8") (pinfunction "SCLK_8") (pintype "input"))
      (node (ref "U6") (pin "35") (pinfunction "GPIO11_35") (pintype "bidirectional"))
    )
    (net (code "85") (name "SWCLK") (class "Default")
      (node (ref "U10") (pin "49") (pinfunction "PA14_49") (pintype "bidirectional"))
      (node (ref "U6") (pin "69") (pinfunction "GPIO20_69") (pintype "bidirectional"))
    )
    (net (code "86") (name "SWDIO") (class "Default")
      (node (ref "U10") (pin "46") (pinfunction "PA13_46") (pintype "bidirectional"))
      (node (ref "U6") (pin "71") (pinfunction "GPIO21_71") (pintype "bidirectional"))
    )
    (net (code "87") (name "UART2_RX") (class "Default")
      (node (ref "J9") (pin "2") (pinfunction "2_2") (pintype "bidirectional"))
      (node (ref "U6") (pin "72") (pinfunction "GPIO41_72") (pintype "bidirectional"))
    )
    (net (code "88") (name "UART2_TX") (class "Default")
      (node (ref "J9") (pin "1") (pinfunction "1_1") (pintype "bidirectional"))
      (node (ref "U6") (pin "70") (pinfunction "GPIO40_70") (pintype "bidirectional"))
    )
    (net (code "89") (name "USART1_RX") (class "Default")
      (node (ref "J3") (pin "1") (pinfunction "1_1") (pintype "bidirectional"))
      (node (ref "U10") (pin "59") (pinfunction "PB7_59") (pintype "bidirectional"))
      (node (ref "U6") (pin "53") (pinfunction "GPIO15_53") (pintype "bidirectional"))
    )
    (net (code "90") (name "USART1_TX") (class "Default")
      (node (ref "J3") (pin "2") (pinfunction "2_2") (pintype "bidirectional"))
      (node (ref "U6") (pin "51") (pinfunction "GPIO14_51") (pintype "bidirectional"))
    )
    (net (code "91") (name "USB_D_N") (class "Default")
      (node (ref "J4") (pin "4") (pinfunction "4_4") (pintype "bidirectional"))
      (node (ref "U6") (pin "167") (pinfunction "USB_DM_167") (pintype "bidirectional"))
    )
    (net (code "92") (name "USB_D_P") (class "Default")
      (node (ref "J4") (pin "5") (pinfunction "5_5") (pintype "bidirectional"))
      (node (ref "U6") (pin "165") (pinfunction "USB_DP_165") (pintype "bidirectional"))
    )
    (net (code "93") (name "unconnected-(U3-FLAG3-Pad4)") (class "Default")
      (node (ref "U3") (pin "4") (pinfunction "FLAG3_4") (pintype "passive"))
    )
    (net (code "94") (name "unconnected-(U4-1_SAFEBOOT_N-Pad1)") (class "Default")
      (node (ref "U4") (pin "1") (pinfunction "1_SAFEBOOT_N_1") (pintype "bidirectional"))
    )
    (net (code "95") (name "unconnected-(U4-2_D_SEL-Pad2)") (class "Default")
      (node (ref "U4") (pin "2") (pinfunction "2_D_SEL_2") (pintype "bidirectional"))
    )
    (net (code "96") (name "unconnected-(U4-3_TIMEPULSE-Pad3)") (class "Default")
      (node (ref "U4") (pin "3") (pinfunction "3_TIMEPULSE_3") (pintype "bidirectional"))
    )
    (net (code "97") (name "unconnected-(U4-4_EXTINT-Pad4)") (class "Default")
      (node (ref "U4") (pin "4") (pinfunction "4_EXTINT_4") (pintype "bidirectional"))
    )
    (net (code "98") (name "unconnected-(U4-5_USB_DM-Pad5)") (class "Default")
      (node (ref "U4") (pin "5") (pinfunction "5_USB_DM_5") (pintype "bidirectional"))
    )
    (net (code "99") (name "unconnected-(U4-6_USB_DP-Pad6)") (class "Default")
      (node (ref "U4") (pin "6") (pinfunction "6_USB_DP_6") (pintype "bidirectional"))
    )
    (net (code "100") (name "unconnected-(U4-8_RESET_N-Pad8)") (class "Default")
      (node (ref "U4") (pin "8") (pinfunction "8_RESET_N_8") (pintype "bidirectional"))
    )
    (net (code "101") (name "unconnected-(U4-14_LNA_EN{slash}RESERVED-Pad14)") (class "Default")
      (node (ref "U4") (pin "14") (pinfunction "14_LNA_EN/RESERVED_14") (pintype "bidirectional"))
    )
    (net (code "102") (name "unconnected-(U4-15_RESERVED-Pad15)") (class "Default")
      (node (ref "U4") (pin "15") (pinfunction "15_RESERVED_15") (pintype "bidirectional"))
    )
    (net (code "103") (name "unconnected-(U4-16_RESERVED-Pad16)") (class "Default")
      (node (ref "U4") (pin "16") (pinfunction "16_RESERVED_16") (pintype "bidirectional"))
    )
    (net (code "104") (name "unconnected-(U4-17_RESERVED-Pad17)") (class "Default")
      (node (ref "U4") (pin "17") (pinfunction "17_RESERVED_17") (pintype "bidirectional"))
    )
    (net (code "105") (name "unconnected-(U4-20_TXD{slash}SPI_MISO-Pad20)") (class "Default")
      (node (ref "U4") (pin "20") (pinfunction "20_TXD/SPI_MISO_20") (pintype "bidirectional"))
    )
    (net (code "106") (name "unconnected-(U4-21_RXD{slash}SPI_MOSI-Pad21)") (class "Default")
      (node (ref "U4") (pin "21") (pinfunction "21_RXD/SPI_MOSI_21") (pintype "bidirectional"))
    )
    (net (code "107") (name "unconnected-(U5-PG-Pad4)") (class "Default")
      (node (ref "U5") (pin "4") (pinfunction "PG_4") (pintype "bidirectional"))
    )
    (net (code "108") (name "unconnected-(U6-CAM1_DN2-Pad143)") (class "Default")
      (node (ref "U6") (pin "143") (pinfunction "CAM1_DN2_143") (pintype "bidirectional"))
    )
    (net (code "109") (name "unconnected-(U6-CAM1_DN3-Pad137)") (class "Default")
      (node (ref "U6") (pin "137") (pinfunction "CAM1_DN3_137") (pintype "bidirectional"))
    )
    (net (code "110") (name "unconnected-(U6-CAM1_DP2-Pad141)") (class "Default")
      (node (ref "U6") (pin "141") (pinfunction "CAM1_DP2_141") (pintype "bidirectional"))
    )
    (net (code "111") (name "unconnected-(U6-CAM1_DP3-Pad135)") (class "Default")
      (node (ref "U6") (pin "135") (pinfunction "CAM1_DP3_135") (pintype "bidirectional"))
    )
    (net (code "112") (name "unconnected-(U6-DSI0_CN-Pad105)") (class "Default")
      (node (ref "U6") (pin "105") (pinfunction "DSI0_CN_105") (pintype "bidirectional"))
    )
    (net (code "113") (name "unconnected-(U6-DSI0_CP-Pad107)") (class "Default")
      (node (ref "U6") (pin "107") (pinfunction "DSI0_CP_107") (pintype "bidirectional"))
    )
    (net (code "114") (name "unconnected-(U6-DSI0_DN0-Pad99)") (class "Default")
      (node (ref "U6") (pin "99") (pinfunction "DSI0_DN0_99") (pintype "bidirectional"))
    )
    (net (code "115") (name "unconnected-(U6-DSI0_DN1-Pad93)") (class "Default")
      (node (ref "U6") (pin "93") (pinfunction "DSI0_DN1_93") (pintype "bidirectional"))
    )
    (net (code "116") (name "unconnected-(U6-DSI0_DP0-Pad101)") (class "Default")
      (node (ref "U6") (pin "101") (pinfunction "DSI0_DP0_101") (pintype "bidirectional"))
    )
    (net (code "117") (name "unconnected-(U6-DSI0_DP1-Pad95)") (class "Default")
      (node (ref "U6") (pin "95") (pinfunction "DSI0_DP1_95") (pintype "bidirectional"))
    )
    (net (code "118") (name "unconnected-(U6-DSI1_CN-Pad102)") (class "Default")
      (node (ref "U6") (pin "102") (pinfunction "DSI1_CN_102") (pintype "bidirectional"))
    )
    (net (code "119") (name "unconnected-(U6-DSI1_CP-Pad100)") (class "Default")
      (node (ref "U6") (pin "100") (pinfunction "DSI1_CP_100") (pintype "bidirectional"))
    )
    (net (code "120") (name "unconnected-(U6-DSI1_DN0-Pad96)") (class "Default")
      (node (ref "U6") (pin "96") (pinfunction "DSI1_DN0_96") (pintype "bidirectional"))
    )
    (net (code "121") (name "unconnected-(U6-DSI1_DN1-Pad120)") (class "Default")
      (node (ref "U6") (pin "120") (pinfunction "DSI1_DN1_120") (pintype "bidirectional"))
    )
    (net (code "122") (name "unconnected-(U6-DSI1_DN2-Pad114)") (class "Default")
      (node (ref "U6") (pin "114") (pinfunction "DSI1_DN2_114") (pintype "bidirectional"))
    )
    (net (code "123") (name "unconnected-(U6-DSI1_DN3-Pad108)") (class "Default")
      (node (ref "U6") (pin "108") (pinfunction "DSI1_DN3_108") (pintype "bidirectional"))
    )
    (net (code "124") (name "unconnected-(U6-DSI1_DP0-Pad94)") (class "Default")
      (node (ref "U6") (pin "94") (pinfunction "DSI1_DP0_94") (pintype "bidirectional"))
    )
    (net (code "125") (name "unconnected-(U6-DSI1_DP1-Pad118)") (class "Default")
      (node (ref "U6") (pin "118") (pinfunction "DSI1_DP1_118") (pintype "bidirectional"))
    )
    (net (code "126") (name "unconnected-(U6-DSI1_DP2-Pad112)") (class "Default")
      (node (ref "U6") (pin "112") (pinfunction "DSI1_DP2_112") (pintype "bidirectional"))
    )
    (net (code "127") (name "unconnected-(U6-DSI1_DP3-Pad106)") (class "Default")
      (node (ref "U6") (pin "106") (pinfunction "DSI1_DP3_106") (pintype "bidirectional"))
    )
    (net (code "128") (name "unconnected-(U6-EMMC_EN_N_1V8-Pad90)") (class "Default")
      (node (ref "U6") (pin "90") (pinfunction "EMMC_EN_N_1V8_90") (pintype "bidirectional"))
    )
    (net (code "129") (name "unconnected-(U6-GPIO5-Pad17)") (class "Default")
      (node (ref "U6") (pin "17") (pinfunction "GPIO5_17") (pintype "bidirectional"))
    )
    (net (code "130") (name "unconnected-(U6-GPIO6-Pad21)") (class "Default")
      (node (ref "U6") (pin "21") (pinfunction "GPIO6_21") (pintype "bidirectional"))
    )
    (net (code "131") (name "unconnected-(U6-GPIO16-Pad57)") (class "Default")
      (node (ref "U6") (pin "57") (pinfunction "GPIO16_57") (pintype "bidirectional"))
    )
    (net (code "132") (name "unconnected-(U6-GPIO17-Pad59)") (class "Default")
      (node (ref "U6") (pin "59") (pinfunction "GPIO17_59") (pintype "bidirectional"))
    )
    (net (code "133") (name "unconnected-(U6-GPIO19-Pad65)") (class "Default")
      (node (ref "U6") (pin "65") (pinfunction "GPIO19_65") (pintype "bidirectional"))
    )
    (net (code "134") (name "unconnected-(U6-GPIO32-Pad46)") (class "Default")
      (node (ref "U6") (pin "46") (pinfunction "GPIO32_46") (pintype "bidirectional"))
    )
    (net (code "135") (name "unconnected-(U6-GPIO33-Pad48)") (class "Default")
      (node (ref "U6") (pin "48") (pinfunction "GPIO33_48") (pintype "bidirectional"))
    )
    (net (code "136") (name "unconnected-(U6-GPIO34-Pad52)") (class "Default")
      (node (ref "U6") (pin "52") (pinfunction "GPIO34_52") (pintype "bidirectional"))
    )
    (net (code "137") (name "unconnected-(U6-GPIO35-Pad54)") (class "Default")
      (node (ref "U6") (pin "54") (pinfunction "GPIO35_54") (pintype "bidirectional"))
    )
    (net (code "138") (name "unconnected-(U6-GPIO36-Pad58)") (class "Default")
      (node (ref "U6") (pin "58") (pinfunction "GPIO36_58") (pintype "bidirectional"))
    )
    (net (code "139") (name "unconnected-(U6-GPIO37-Pad60)") (class "Default")
      (node (ref "U6") (pin "60") (pinfunction "GPIO37_60") (pintype "bidirectional"))
    )
    (net (code "140") (name "unconnected-(U6-GPIO45-Pad84)") (class "Default")
      (node (ref "U6") (pin "84") (pinfunction "GPIO45_84") (pintype "bidirectional"))
    )
    (net (code "141") (name "unconnected-(U6-HDMI_CEC-Pad171)") (class "Default")
      (node (ref "U6") (pin "171") (pinfunction "HDMI_CEC_171") (pintype "bidirectional"))
    )
    (net (code "142") (name "unconnected-(U6-HDMI_CK_N-Pad111)") (class "Default")
      (node (ref "U6") (pin "111") (pinfunction "HDMI_CK_N_111") (pintype "bidirectional"))
    )
    (net (code "143") (name "unconnected-(U6-HDMI_CK_P-Pad113)") (class "Default")
      (node (ref "U6") (pin "113") (pinfunction "HDMI_CK_P_113") (pintype "bidirectional"))
    )
    (net (code "144") (name "unconnected-(U6-HDMI_D0_N-Pad117)") (class "Default")
      (node (ref "U6") (pin "117") (pinfunction "HDMI_D0_N_117") (pintype "bidirectional"))
    )
    (net (code "145") (name "unconnected-(U6-HDMI_D0_P-Pad119)") (class "Default")
      (node (ref "U6") (pin "119") (pinfunction "HDMI_D0_P_119") (pintype "bidirectional"))
    )
    (net (code "146") (name "unconnected-(U6-HDMI_D1_N-Pad123)") (class "Default")
      (node (ref "U6") (pin "123") (pinfunction "HDMI_D1_N_123") (pintype "bidirectional"))
    )
    (net (code "147") (name "unconnected-(U6-HDMI_D1_P-Pad125)") (class "Default")
      (node (ref "U6") (pin "125") (pinfunction "HDMI_D1_P_125") (pintype "bidirectional"))
    )
    (net (code "148") (name "unconnected-(U6-HDMI_D2_N-Pad129)") (class "Default")
      (node (ref "U6") (pin "129") (pinfunction "HDMI_D2_N_129") (pintype "bidirectional"))
    )
    (net (code "149") (name "unconnected-(U6-HDMI_D2_P-Pad131)") (class "Default")
      (node (ref "U6") (pin "131") (pinfunction "HDMI_D2_P_131") (pintype "bidirectional"))
    )
    (net (code "150") (name "unconnected-(U6-HDMI_HPD_N_1V8-Pad88)") (class "Default")
      (node (ref "U6") (pin "88") (pinfunction "HDMI_HPD_N_1V8_88") (pintype "bidirectional"))
    )
    (net (code "151") (name "unconnected-(U6-HDMI_SCL-Pad175)") (class "Default")
      (node (ref "U6") (pin "175") (pinfunction "HDMI_SCL_175") (pintype "bidirectional"))
    )
    (net (code "152") (name "unconnected-(U6-HDMI_SDA-Pad173)") (class "Default")
      (node (ref "U6") (pin "173") (pinfunction "HDMI_SDA_173") (pintype "bidirectional"))
    )
    (net (code "153") (name "unconnected-(U6-NC-Pad124)") (class "Default")
      (node (ref "U6") (pin "124") (pinfunction "NC_124") (pintype "bidirectional"))
    )
    (net (code "154") (name "unconnected-(U6-NC-Pad126)") (class "Default")
      (node (ref "U6") (pin "126") (pinfunction "NC_126") (pintype "bidirectional"))
    )
    (net (code "155") (name "unconnected-(U6-NC-Pad128)") (class "Default")
      (node (ref "U6") (pin "128") (pinfunction "NC_128") (pintype "bidirectional"))
    )
    (net (code "156") (name "unconnected-(U6-NC-Pad130)") (class "Default")
      (node (ref "U6") (pin "130") (pinfunction "NC_130") (pintype "bidirectional"))
    )
    (net (code "157") (name "unconnected-(U6-NC-Pad132)") (class "Default")
      (node (ref "U6") (pin "132") (pinfunction "NC_132") (pintype "bidirectional"))
    )
    (net (code "158") (name "unconnected-(U6-NC-Pad154)") (class "Default")
      (node (ref "U6") (pin "154") (pinfunction "NC_154") (pintype "bidirectional"))
    )
    (net (code "159") (name "unconnected-(U6-NC-Pad156)") (class "Default")
      (node (ref "U6") (pin "156") (pinfunction "NC_156") (pintype "bidirectional"))
    )
    (net (code "160") (name "unconnected-(U6-NC-Pad158)") (class "Default")
      (node (ref "U6") (pin "158") (pinfunction "NC_158") (pintype "bidirectional"))
    )
    (net (code "161") (name "unconnected-(U6-NC-Pad160)") (class "Default")
      (node (ref "U6") (pin "160") (pinfunction "NC_160") (pintype "bidirectional"))
    )
    (net (code "162") (name "unconnected-(U6-NC-Pad162)") (class "Default")
      (node (ref "U6") (pin "162") (pinfunction "NC_162") (pintype "bidirectional"))
    )
    (net (code "163") (name "unconnected-(U6-RUN-Pad177)") (class "Default")
      (node (ref "U6") (pin "177") (pinfunction "RUN_177") (pintype "bidirectional"))
    )
    (net (code "164") (name "unconnected-(U6-TVDAC-Pad166)") (class "Default")
      (node (ref "U6") (pin "166") (pinfunction "TVDAC_166") (pintype "bidirectional"))
    )
    (net (code "165") (name "unconnected-(U6-VC_TCK-Pad180)") (class "Default")
      (node (ref "U6") (pin "180") (pinfunction "VC_TCK_180") (pintype "bidirectional"))
    )
    (net (code "166") (name "unconnected-(U6-VC_TDI-Pad174)") (class "Default")
      (node (ref "U6") (pin "174") (pinfunction "VC_TDI_174") (pintype "bidirectional"))
    )
    (net (code "167") (name "unconnected-(U6-VC_TDO-Pad178)") (class "Default")
      (node (ref "U6") (pin "178") (pinfunction "VC_TDO_178") (pintype "bidirectional"))
    )
    (net (code "168") (name "unconnected-(U6-VC_TMS-Pad176)") (class "Default")
      (node (ref "U6") (pin "176") (pinfunction "VC_TMS_176") (pintype "bidirectional"))
    )
    (net (code "169") (name "unconnected-(U6-VC_TRST_N-Pad172)") (class "Default")
      (node (ref "U6") (pin "172") (pinfunction "VC_TRST_N_172") (pintype "bidirectional"))
    )
    (net (code "170") (name "unconnected-(U6-VDAC-Pad189)") (class "Default")
      (node (ref "U6") (pin "189") (pinfunction "VDAC_189") (pintype "bidirectional"))
    )
    (net (code "171") (name "unconnected-(U6-VDAC-Pad190)") (class "Default")
      (node (ref "U6") (pin "190") (pinfunction "VDAC_190") (pintype "bidirectional"))
    )
    (net (code "172") (name "unconnected-(U6-VDD_CORE-Pad179)") (class "Default")
      (node (ref "U6") (pin "179") (pinfunction "VDD_CORE_179") (pintype "bidirectional"))
    )
    (net (code "173") (name "unconnected-(U7-NC-Pad3)") (class "Default")
      (node (ref "U7") (pin "3") (pinfunction "NC_3") (pintype "bidirectional"))
    )
    (net (code "174") (name "unconnected-(U10-PA0-Pad14)") (class "Default")
      (node (ref "U10") (pin "14") (pinfunction "PA0_14") (pintype "bidirectional"))
    )
    (net (code "175") (name "unconnected-(U10-PA1-Pad15)") (class "Default")
      (node (ref "U10") (pin "15") (pinfunction "PA1_15") (pintype "bidirectional"))
    )
    (net (code "176") (name "unconnected-(U10-PA2-Pad16)") (class "Default")
      (node (ref "U10") (pin "16") (pinfunction "PA2_16") (pintype "bidirectional"))
    )
    (net (code "177") (name "unconnected-(U10-PA3-Pad17)") (class "Default")
      (node (ref "U10") (pin "17") (pinfunction "PA3_17") (pintype "bidirectional"))
    )
    (net (code "178") (name "unconnected-(U10-PA8-Pad41)") (class "Default")
      (node (ref "U10") (pin "41") (pinfunction "PA8_41") (pintype "bidirectional"))
    )
    (net (code "179") (name "unconnected-(U10-PA9-Pad42)") (class "Default")
      (node (ref "U10") (pin "42") (pinfunction "PA9_42") (pintype "bidirectional"))
    )
    (net (code "180") (name "unconnected-(U10-PA10-Pad43)") (class "Default")
      (node (ref "U10") (pin "43") (pinfunction "PA10_43") (pintype "bidirectional"))
    )
    (net (code "181") (name "unconnected-(U10-PA11-Pad44)") (class "Default")
      (node (ref "U10") (pin "44") (pinfunction "PA11_44") (pintype "bidirectional"))
    )
    (net (code "182") (name "unconnected-(U10-PA12-Pad45)") (class "Default")
      (node (ref "U10") (pin "45") (pinfunction "PA12_45") (pintype "bidirectional"))
    )
    (net (code "183") (name "unconnected-(U10-PA15-Pad50)") (class "Default")
      (node (ref "U10") (pin "50") (pinfunction "PA15_50") (pintype "bidirectional"))
    )
    (net (code "184") (name "unconnected-(U10-PB2-Pad28)") (class "Default")
      (node (ref "U10") (pin "28") (pinfunction "PB2_28") (pintype "bidirectional"))
    )
    (net (code "185") (name "unconnected-(U10-PB3-Pad55)") (class "Default")
      (node (ref "U10") (pin "55") (pinfunction "PB3_55") (pintype "bidirectional"))
    )
    (net (code "186") (name "unconnected-(U10-PB4-Pad56)") (class "Default")
      (node (ref "U10") (pin "56") (pinfunction "PB4_56") (pintype "bidirectional"))
    )
    (net (code "187") (name "unconnected-(U10-PB5-Pad57)") (class "Default")
      (node (ref "U10") (pin "57") (pinfunction "PB5_57") (pintype "bidirectional"))
    )
    (net (code "188") (name "unconnected-(U10-PB6-Pad58)") (class "Default")
      (node (ref "U10") (pin "58") (pinfunction "PB6_58") (pintype "bidirectional"))
    )
    (net (code "189") (name "unconnected-(U10-PB10-Pad29)") (class "Default")
      (node (ref "U10") (pin "29") (pinfunction "PB10_29") (pintype "bidirectional"))
    )
    (net (code "190") (name "unconnected-(U10-PB12-Pad33)") (class "Default")
      (node (ref "U10") (pin "33") (pinfunction "PB12_33") (pintype "bidirectional"))
    )
    (net (code "191") (name "unconnected-(U10-PB13-Pad34)") (class "Default")
      (node (ref "U10") (pin "34") (pinfunction "PB13_34") (pintype "bidirectional"))
    )
    (net (code "192") (name "unconnected-(U10-PB14-Pad35)") (class "Default")
      (node (ref "U10") (pin "35") (pinfunction "PB14_35") (pintype "bidirectional"))
    )
    (net (code "193") (name "unconnected-(U10-PB15-Pad36)") (class "Default")
      (node (ref "U10") (pin "36") (pinfunction "PB15_36") (pintype "bidirectional"))
    )
    (net (code "194") (name "unconnected-(U10-PC0-Pad8)") (class "Default")
      (node (ref "U10") (pin "8") (pinfunction "PC0_8") (pintype "bidirectional"))
    )
    (net (code "195") (name "unconnected-(U10-PC1-Pad9)") (class "Default")
      (node (ref "U10") (pin "9") (pinfunction "PC1_9") (pintype "bidirectional"))
    )
    (net (code "196") (name "unconnected-(U10-PC2-Pad10)") (class "Default")
      (node (ref "U10") (pin "10") (pinfunction "PC2_10") (pintype "bidirectional"))
    )
    (net (code "197") (name "unconnected-(U10-PC3-Pad11)") (class "Default")
      (node (ref "U10") (pin "11") (pinfunction "PC3_11") (pintype "bidirectional"))
    )
    (net (code "198") (name "unconnected-(U10-PC6-Pad37)") (class "Default")
      (node (ref "U10") (pin "37") (pinfunction "PC6_37") (pintype "bidirectional"))
    )
    (net (code "199") (name "unconnected-(U10-PC7-Pad38)") (class "Default")
      (node (ref "U10") (pin "38") (pinfunction "PC7_38") (pintype "bidirectional"))
    )
    (net (code "200") (name "unconnected-(U10-PC8-Pad39)") (class "Default")
      (node (ref "U10") (pin "39") (pinfunction "PC8_39") (pintype "bidirectional"))
    )
    (net (code "201") (name "unconnected-(U10-PC9-Pad40)") (class "Default")
      (node (ref "U10") (pin "40") (pinfunction "PC9_40") (pintype "bidirectional"))
    )
    (net (code "202") (name "unconnected-(U10-PC10-Pad51)") (class "Default")
      (node (ref "U10") (pin "51") (pinfunction "PC10_51") (pintype "bidirectional"))
    )
    (net (code "203") (name "unconnected-(U10-PC11-Pad52)") (class "Default")
      (node (ref "U10") (pin "52") (pinfunction "PC11_52") (pintype "bidirectional"))
    )
    (net (code "204") (name "unconnected-(U10-PC12-Pad53)") (class "Default")
      (node (ref "U10") (pin "53") (pinfunction "PC12_53") (pintype "bidirectional"))
    )
    (net (code "205") (name "unconnected-(U10-PC13-Pad2)") (class "Default")
      (node (ref "U10") (pin "2") (pinfunction "PC13_2") (pintype "bidirectional"))
    )
    (net (code "206") (name "unconnected-(U10-PC14-Pad3)") (class "Default")
      (node (ref "U10") (pin "3") (pinfunction "PC14_3") (pintype "bidirectional"))
    )
    (net (code "207") (name "unconnected-(U10-PC15-Pad4)") (class "Default")
      (node (ref "U10") (pin "4") (pinfunction "PC15_4") (pintype "bidirectional"))
    )
    (net (code "208") (name "unconnected-(U10-PD2-Pad54)") (class "Default")
      (node (ref "U10") (pin "54") (pinfunction "PD2_54") (pintype "bidirectional"))
    )
    (net (code "209") (name "unconnected-(U10-PH0-OSC_IN-Pad5)") (class "Default")
      (node (ref "U10") (pin "5") (pinfunction "PH0-OSC_IN_5") (pintype "bidirectional"))
    )
    (net (code "210") (name "unconnected-(U10-PH1-OSC_OUT-Pad6)") (class "Default")
      (node (ref "U10") (pin "6") (pinfunction "PH1-OSC_OUT_6") (pintype "bidirectional"))
    )
    (net (code "211") (name "unconnected-(U11-PadADC)") (class "Default")
      (node (ref "U11") (pin "ADC") (pinfunction "ADC_ADC") (pintype "bidirectional"))
    )
    (net (code "212") (name "unconnected-(U11-PadGPIO0)") (class "Default")
      (node (ref "U11") (pin "GPIO0") (pinfunction "GPIO0_GPIO0") (pintype "bidirectional"))
    )
    (net (code "213") (name "unconnected-(U11-PadGPIO2)") (class "Default")
      (node (ref "U11") (pin "GPIO2") (pinfunction "GPIO2_GPIO2") (pintype "bidirectional"))
    )
    (net (code "214") (name "unconnected-(U11-PadGPIO5)") (class "Default")
      (node (ref "U11") (pin "GPIO5") (pinfunction "GPIO5_GPIO5") (pintype "bidirectional"))
    )
    (net (code "215") (name "unconnected-(U11-PadGPIO12)") (class "Default")
      (node (ref "U11") (pin "GPIO12") (pinfunction "GPIO12_GPIO12") (pintype "bidirectional"))
    )
    (net (code "216") (name "unconnected-(U11-PadGPIO13)") (class "Default")
      (node (ref "U11") (pin "GPIO13") (pinfunction "GPIO13_GPIO13") (pintype "bidirectional"))
    )
    (net (code "217") (name "unconnected-(U11-PadGPIO14)") (class "Default")
      (node (ref "U11") (pin "GPIO14") (pinfunction "GPIO14_GPIO14") (pintype "bidirectional"))
    )
    (net (code "218") (name "unconnected-(U11-PadGPIO15)") (class "Default")
      (node (ref "U11") (pin "GPIO15") (pinfunction "GPIO15_GPIO15") (pintype "bidirectional"))
    )
    (net (code "219") (name "unconnected-(U11-PadGPIO16)") (class "Default")
      (node (ref "U11") (pin "GPIO16") (pinfunction "GPIO16_GPIO16") (pintype "bidirectional"))
    )
    (net (code "220") (name "unconnected-(U11-PadRESET)") (class "Default")
      (node (ref "U11") (pin "RESET") (pinfunction "RESET_RESET") (pintype "bidirectional"))
    )
    (net (code "221") (name "unconnected-(U11-RX-PadRXD0)") (class "Default")
      (node (ref "U11") (pin "RXD0") (pinfunction "RX_RXD0") (pintype "bidirectional"))
    )
    (net (code "222") (name "unconnected-(U11-TX-PadTXD0)") (class "Default")
      (node (ref "U11") (pin "TXD0") (pinfunction "TX_TXD0") (pintype "bidirectional"))
    )
  )
)
